# Uno.net
KiCad netlist of a schematic drawn in Altium Designer
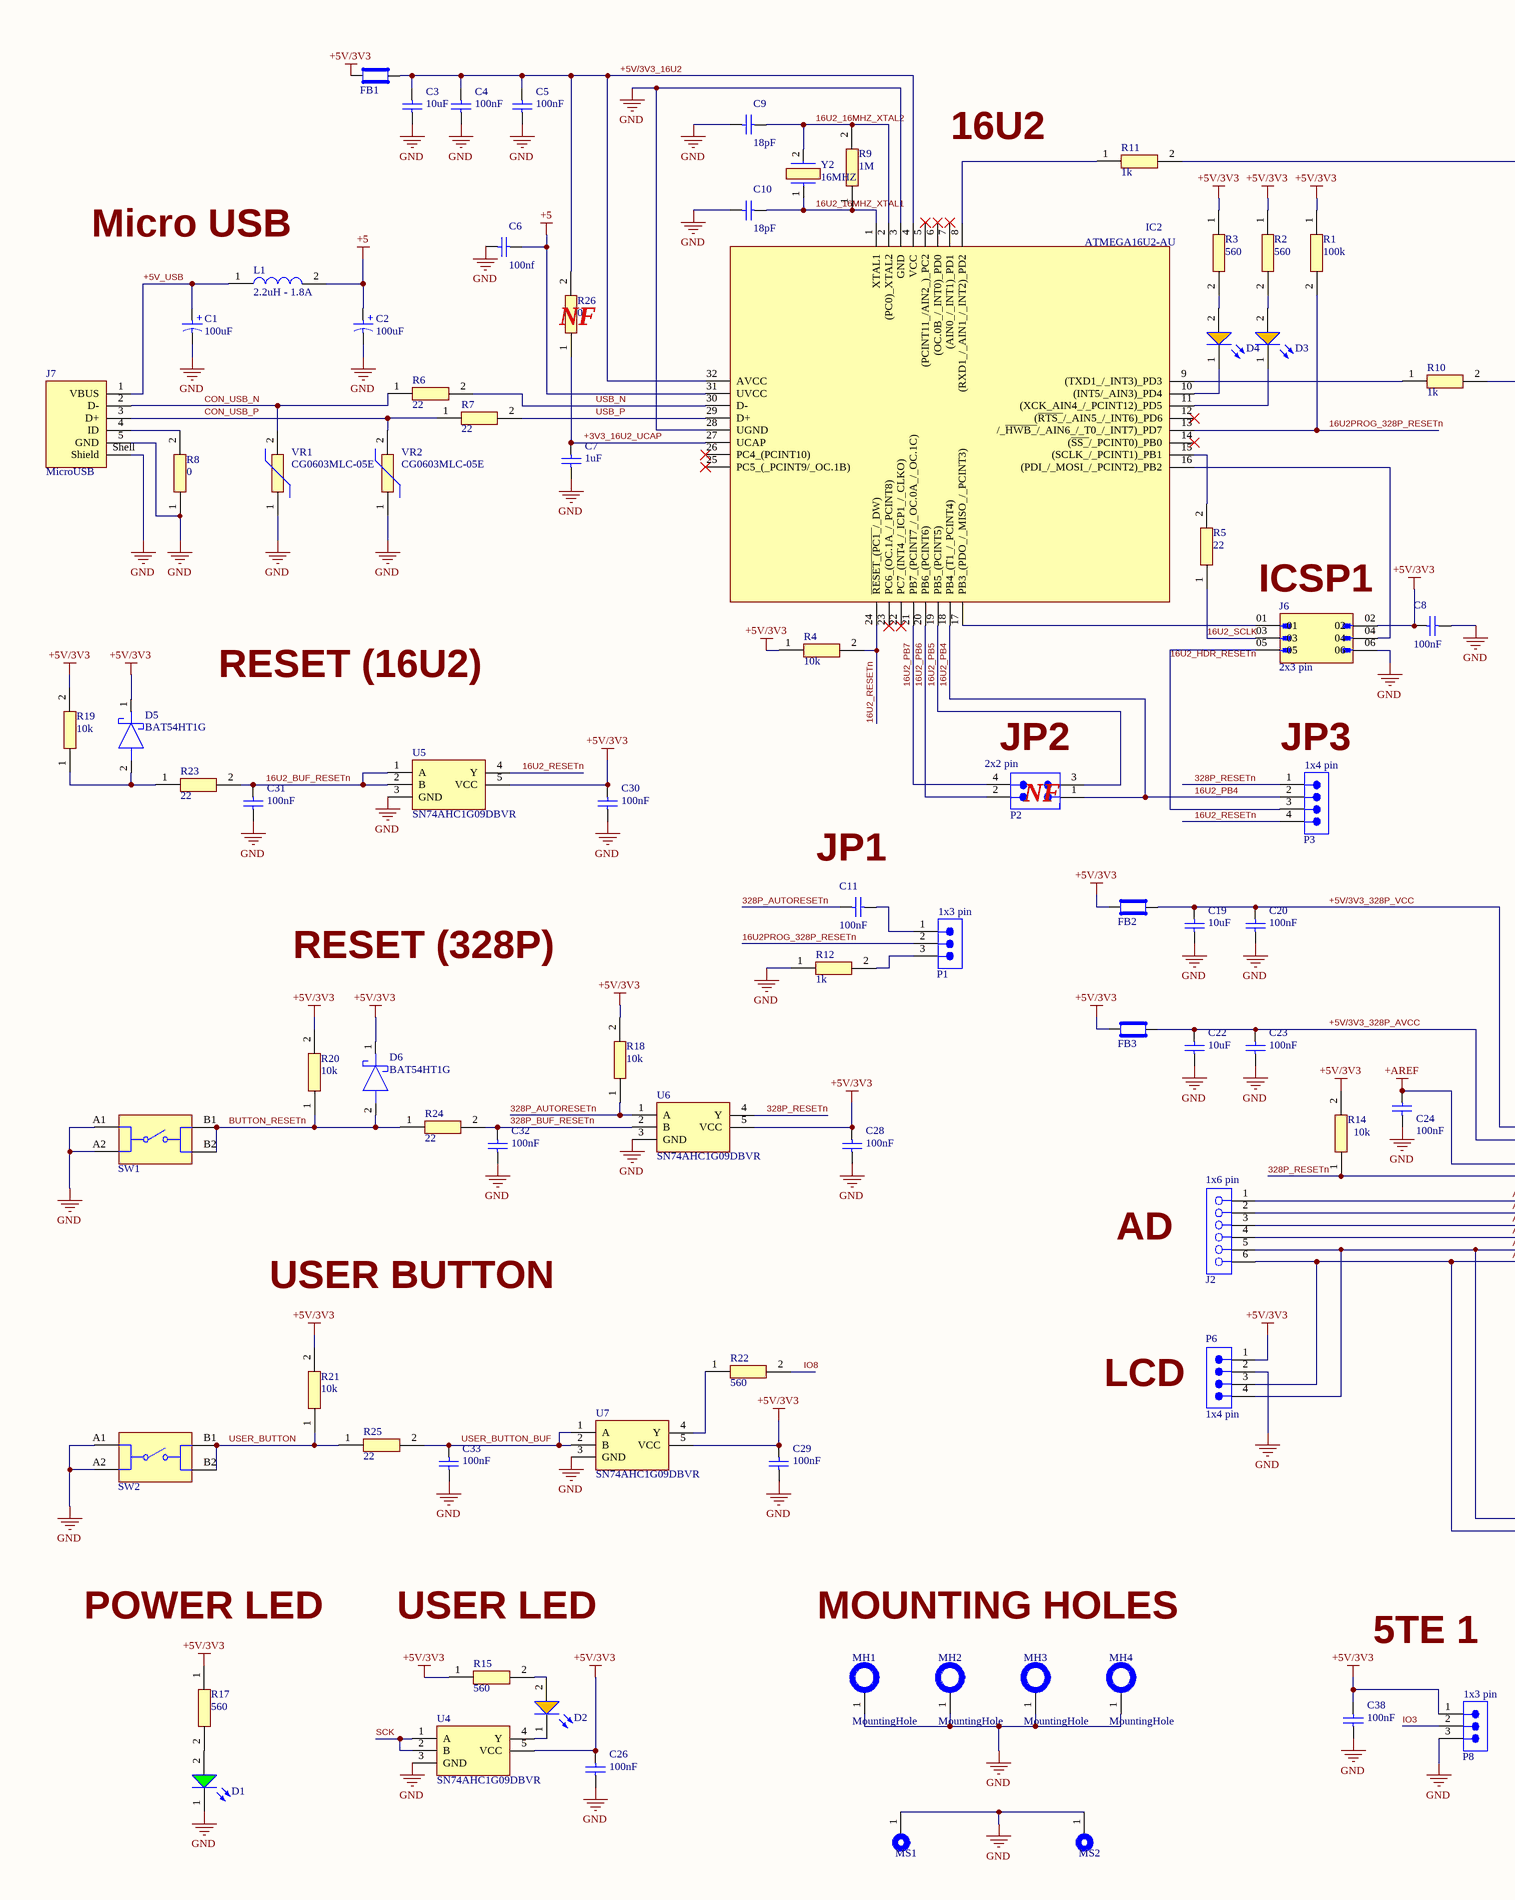
[diagram p0: Uno.SchDoc, left]
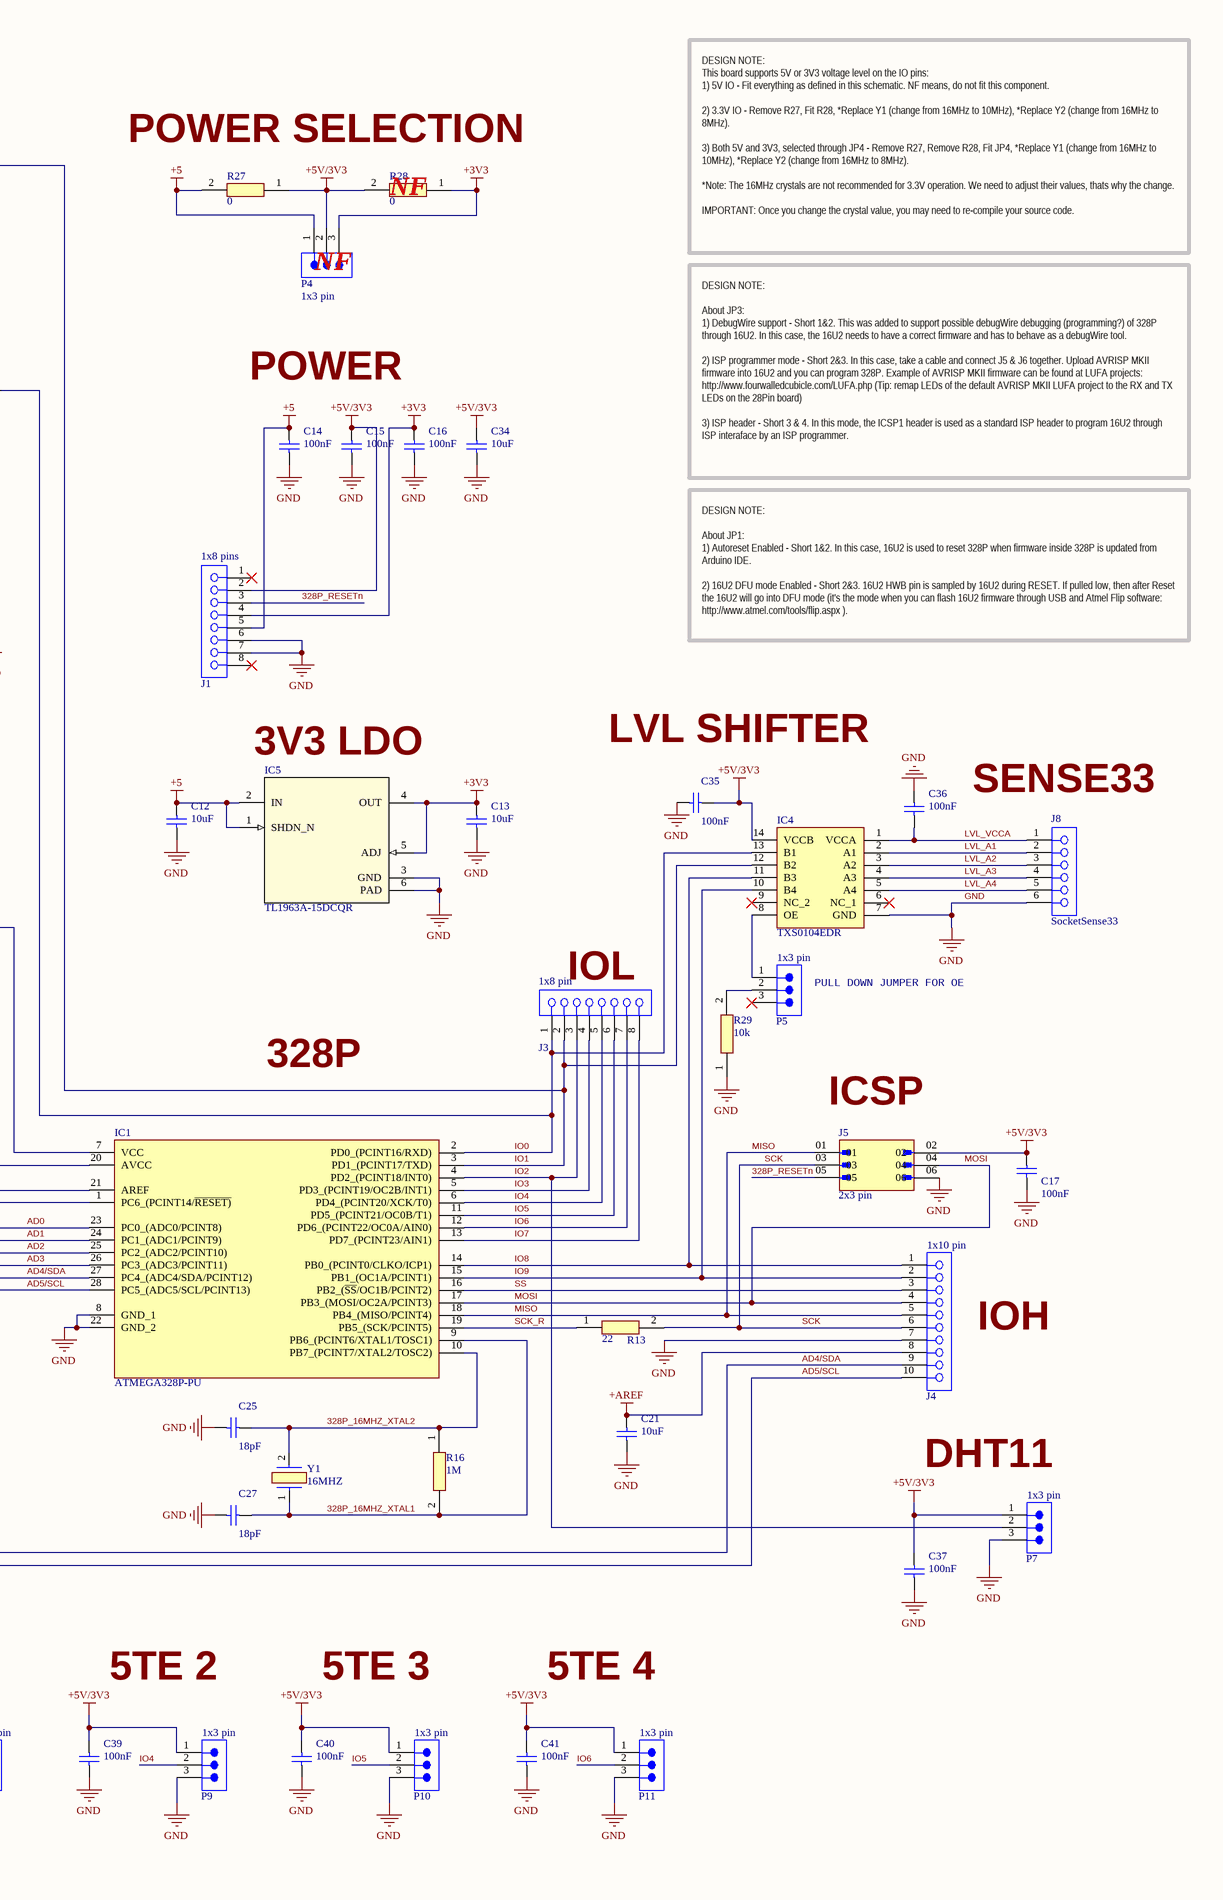
[diagram p1: Uno.SchDoc, right]

(export (version "E")
  (design (tool "Eeschema 10.0.6"))
  (components
    (comp (ref "C1")
      (value "100uF")
      (footprint "GH_PcbLib:WCAP-ASLI_D6.3H5.5")
      (description "WCAP-ASLI Aluminum Electrolytic Capacitor, V-Chip, D6.3 x H5.5mm, 100uF, 10V")
      (fields
        (field (name "MANUFACTURER PART NUMBER") "865080243007")
        (field (name "MANUFACTURER") "Wurth Elektronik")
      )
      (libsource (lib "GH_SchematicLib") (part "865080243007"))
    )
    (comp (ref "C2")
      (value "100uF")
      (footprint "GH_PcbLib:WCAP-ASLI_D6.3H5.5")
      (description "WCAP-ASLI Aluminum Electrolytic Capacitor, V-Chip, D6.3 x H5.5mm, 100uF, 10V")
      (fields
        (field (name "MANUFACTURER PART NUMBER") "865080243007")
        (field (name "MANUFACTURER") "Wurth Elektronik")
      )
      (libsource (lib "GH_SchematicLib") (part "865080243007"))
    )
    (comp (ref "C3")
      (value "10uF")
      (footprint "GH_PcbLib:WCAP_0805_L2W1.25H0.8")
      (fields
        (field (name "MANUFACTURER PART NUMBER") "885012004001")
        (field (name "MANUFACTURER") "Wurth Elektronik")
      )
      (libsource (lib "GH_SchematicLib") (part "CeramicCap"))
    )
    (comp (ref "C4")
      (value "100nF")
      (footprint "GH_PcbLib:WCAP_0805_L2W1.25H0.8")
      (fields
        (field (name "MANUFACTURER PART NUMBER") "885012004001")
        (field (name "MANUFACTURER") "Wurth Elektronik")
      )
      (libsource (lib "GH_SchematicLib") (part "CeramicCap"))
    )
    (comp (ref "C5")
      (value "100nF")
      (footprint "GH_PcbLib:WCAP_0805_L2W1.25H0.8")
      (fields
        (field (name "MANUFACTURER PART NUMBER") "885012004001")
        (field (name "MANUFACTURER") "Wurth Elektronik")
      )
      (libsource (lib "GH_SchematicLib") (part "CeramicCap"))
    )
    (comp (ref "C6")
      (value "100nf")
      (footprint "GH_PcbLib:WCAP_0805_L2W1.25H0.8")
      (fields
        (field (name "MANUFACTURER PART NUMBER") "885012004001")
        (field (name "MANUFACTURER") "Wurth Elektronik")
      )
      (libsource (lib "GH_SchematicLib") (part "CeramicCap"))
    )
    (comp (ref "C7")
      (value "1uF")
      (footprint "GH_PcbLib:WCAP_0805_L2W1.25H0.8")
      (fields
        (field (name "MANUFACTURER PART NUMBER") "885012004001")
        (field (name "MANUFACTURER") "Wurth Elektronik")
      )
      (libsource (lib "GH_SchematicLib") (part "CeramicCap"))
    )
    (comp (ref "C8")
      (value "100nF")
      (footprint "GH_PcbLib:WCAP_0805_L2W1.25H0.8")
      (fields
        (field (name "MANUFACTURER PART NUMBER") "885012004001")
        (field (name "MANUFACTURER") "Wurth Elektronik")
      )
      (libsource (lib "GH_SchematicLib") (part "CeramicCap"))
    )
    (comp (ref "C9")
      (value "18pF")
      (footprint "GH_PcbLib:WCAP_0805_L2W1.25H0.8")
      (fields
        (field (name "MANUFACTURER PART NUMBER") "885012004001")
        (field (name "MANUFACTURER") "Wurth Elektronik")
      )
      (libsource (lib "GH_SchematicLib") (part "CeramicCap"))
    )
    (comp (ref "C10")
      (value "18pF")
      (footprint "GH_PcbLib:WCAP_0805_L2W1.25H0.8")
      (fields
        (field (name "MANUFACTURER PART NUMBER") "885012004001")
        (field (name "MANUFACTURER") "Wurth Elektronik")
      )
      (libsource (lib "GH_SchematicLib") (part "CeramicCap"))
    )
    (comp (ref "C11")
      (value "100nF")
      (footprint "GH_PcbLib:WCAP_0805_L2W1.25H0.8")
      (fields
        (field (name "MANUFACTURER PART NUMBER") "885012004001")
        (field (name "MANUFACTURER") "Wurth Elektronik")
      )
      (libsource (lib "GH_SchematicLib") (part "CeramicCap"))
    )
    (comp (ref "C12")
      (value "10uF")
      (footprint "GH_PcbLib:WCAP_0805_L2W1.25H0.8")
      (fields
        (field (name "MANUFACTURER PART NUMBER") "885012004001")
        (field (name "MANUFACTURER") "Wurth Elektronik")
      )
      (libsource (lib "GH_SchematicLib") (part "CeramicCap"))
    )
    (comp (ref "C13")
      (value "10uF")
      (footprint "GH_PcbLib:WCAP_0805_L2W1.25H0.8")
      (fields
        (field (name "MANUFACTURER PART NUMBER") "885012004001")
        (field (name "MANUFACTURER") "Wurth Elektronik")
      )
      (libsource (lib "GH_SchematicLib") (part "CeramicCap"))
    )
    (comp (ref "C14")
      (value "100nF")
      (footprint "GH_PcbLib:WCAP_0805_L2W1.25H0.8")
      (fields
        (field (name "MANUFACTURER PART NUMBER") "885012004001")
        (field (name "MANUFACTURER") "Wurth Elektronik")
      )
      (libsource (lib "GH_SchematicLib") (part "CeramicCap"))
    )
    (comp (ref "C15")
      (value "100nF")
      (footprint "GH_PcbLib:WCAP_0805_L2W1.25H0.8")
      (fields
        (field (name "MANUFACTURER PART NUMBER") "885012004001")
        (field (name "MANUFACTURER") "Wurth Elektronik")
      )
      (libsource (lib "GH_SchematicLib") (part "CeramicCap"))
    )
    (comp (ref "C16")
      (value "100nF")
      (footprint "GH_PcbLib:WCAP_0805_L2W1.25H0.8")
      (fields
        (field (name "MANUFACTURER PART NUMBER") "885012004001")
        (field (name "MANUFACTURER") "Wurth Elektronik")
      )
      (libsource (lib "GH_SchematicLib") (part "CeramicCap"))
    )
    (comp (ref "C17")
      (value "100nF")
      (footprint "GH_PcbLib:WCAP_0805_L2W1.25H0.8")
      (fields
        (field (name "MANUFACTURER PART NUMBER") "885012004001")
        (field (name "MANUFACTURER") "Wurth Elektronik")
      )
      (libsource (lib "GH_SchematicLib") (part "CeramicCap"))
    )
    (comp (ref "C19")
      (value "10uF")
      (footprint "GH_PcbLib:WCAP_0805_L2W1.25H0.8")
      (fields
        (field (name "MANUFACTURER PART NUMBER") "885012004001")
        (field (name "MANUFACTURER") "Wurth Elektronik")
      )
      (libsource (lib "GH_SchematicLib") (part "CeramicCap"))
    )
    (comp (ref "C20")
      (value "100nF")
      (footprint "GH_PcbLib:WCAP_0805_L2W1.25H0.8")
      (fields
        (field (name "MANUFACTURER PART NUMBER") "885012004001")
        (field (name "MANUFACTURER") "Wurth Elektronik")
      )
      (libsource (lib "GH_SchematicLib") (part "CeramicCap"))
    )
    (comp (ref "C21")
      (value "10uF")
      (footprint "GH_PcbLib:WCAP_0805_L2W1.25H0.8")
      (fields
        (field (name "MANUFACTURER PART NUMBER") "885012004001")
        (field (name "MANUFACTURER") "Wurth Elektronik")
      )
      (libsource (lib "GH_SchematicLib") (part "CeramicCap"))
    )
    (comp (ref "C22")
      (value "10uF")
      (footprint "GH_PcbLib:WCAP_0805_L2W1.25H0.8")
      (fields
        (field (name "MANUFACTURER PART NUMBER") "885012004001")
        (field (name "MANUFACTURER") "Wurth Elektronik")
      )
      (libsource (lib "GH_SchematicLib") (part "CeramicCap"))
    )
    (comp (ref "C23")
      (value "100nF")
      (footprint "GH_PcbLib:WCAP_0805_L2W1.25H0.8")
      (fields
        (field (name "MANUFACTURER PART NUMBER") "885012004001")
        (field (name "MANUFACTURER") "Wurth Elektronik")
      )
      (libsource (lib "GH_SchematicLib") (part "CeramicCap"))
    )
    (comp (ref "C24")
      (value "100nF")
      (footprint "GH_PcbLib:WCAP_0805_L2W1.25H0.8")
      (fields
        (field (name "MANUFACTURER PART NUMBER") "885012004001")
        (field (name "MANUFACTURER") "Wurth Elektronik")
      )
      (libsource (lib "GH_SchematicLib") (part "CeramicCap"))
    )
    (comp (ref "C25")
      (value "18pF")
      (footprint "GH_PcbLib:WCAP_0805_L2W1.25H0.8")
      (fields
        (field (name "MANUFACTURER PART NUMBER") "885012004001")
        (field (name "MANUFACTURER") "Wurth Elektronik")
      )
      (libsource (lib "GH_SchematicLib") (part "CeramicCap"))
    )
    (comp (ref "C26")
      (value "100nF")
      (footprint "GH_PcbLib:WCAP_0805_L2W1.25H0.8")
      (fields
        (field (name "MANUFACTURER PART NUMBER") "885012004001")
        (field (name "MANUFACTURER") "Wurth Elektronik")
      )
      (libsource (lib "GH_SchematicLib") (part "CeramicCap"))
    )
    (comp (ref "C27")
      (value "18pF")
      (footprint "GH_PcbLib:WCAP_0805_L2W1.25H0.8")
      (fields
        (field (name "MANUFACTURER PART NUMBER") "885012004001")
        (field (name "MANUFACTURER") "Wurth Elektronik")
      )
      (libsource (lib "GH_SchematicLib") (part "CeramicCap"))
    )
    (comp (ref "C28")
      (value "100nF")
      (footprint "GH_PcbLib:WCAP_0805_L2W1.25H0.8")
      (fields
        (field (name "MANUFACTURER PART NUMBER") "885012004001")
        (field (name "MANUFACTURER") "Wurth Elektronik")
      )
      (libsource (lib "GH_SchematicLib") (part "CeramicCap"))
    )
    (comp (ref "C29")
      (value "100nF")
      (footprint "GH_PcbLib:WCAP_0805_L2W1.25H0.8")
      (fields
        (field (name "MANUFACTURER PART NUMBER") "885012004001")
        (field (name "MANUFACTURER") "Wurth Elektronik")
      )
      (libsource (lib "GH_SchematicLib") (part "CeramicCap"))
    )
    (comp (ref "C30")
      (value "100nF")
      (footprint "GH_PcbLib:WCAP_0805_L2W1.25H0.8")
      (fields
        (field (name "MANUFACTURER PART NUMBER") "885012004001")
        (field (name "MANUFACTURER") "Wurth Elektronik")
      )
      (libsource (lib "GH_SchematicLib") (part "CeramicCap"))
    )
    (comp (ref "C31")
      (value "100nF")
      (footprint "GH_PcbLib:WCAP_0805_L2W1.25H0.8")
      (fields
        (field (name "MANUFACTURER PART NUMBER") "885012004001")
        (field (name "MANUFACTURER") "Wurth Elektronik")
      )
      (libsource (lib "GH_SchematicLib") (part "CeramicCap"))
    )
    (comp (ref "C32")
      (value "100nF")
      (footprint "GH_PcbLib:WCAP_0805_L2W1.25H0.8")
      (fields
        (field (name "MANUFACTURER PART NUMBER") "885012004001")
        (field (name "MANUFACTURER") "Wurth Elektronik")
      )
      (libsource (lib "GH_SchematicLib") (part "CeramicCap"))
    )
    (comp (ref "C33")
      (value "100nF")
      (footprint "GH_PcbLib:WCAP_0805_L2W1.25H0.8")
      (fields
        (field (name "MANUFACTURER PART NUMBER") "885012004001")
        (field (name "MANUFACTURER") "Wurth Elektronik")
      )
      (libsource (lib "GH_SchematicLib") (part "CeramicCap"))
    )
    (comp (ref "C34")
      (value "10uF")
      (footprint "GH_PcbLib:WCAP_0805_L2W1.25H0.8")
      (fields
        (field (name "MANUFACTURER PART NUMBER") "885012004001")
        (field (name "MANUFACTURER") "Wurth Elektronik")
      )
      (libsource (lib "GH_SchematicLib") (part "CeramicCap"))
    )
    (comp (ref "C35")
      (value "100nF")
      (footprint "GH_PcbLib:WCAP_0805_L2W1.25H0.8")
      (fields
        (field (name "MANUFACTURER PART NUMBER") "885012004001")
        (field (name "MANUFACTURER") "Wurth Elektronik")
      )
      (libsource (lib "GH_SchematicLib") (part "CeramicCap"))
    )
    (comp (ref "C36")
      (value "100nF")
      (footprint "GH_PcbLib:WCAP_0805_L2W1.25H0.8")
      (fields
        (field (name "MANUFACTURER PART NUMBER") "885012004001")
        (field (name "MANUFACTURER") "Wurth Elektronik")
      )
      (libsource (lib "GH_SchematicLib") (part "CeramicCap"))
    )
    (comp (ref "C37")
      (value "100nF")
      (footprint "GH_PcbLib:WCAP_0805_L2W1.25H0.8")
      (fields
        (field (name "MANUFACTURER PART NUMBER") "885012004001")
        (field (name "MANUFACTURER") "Wurth Elektronik")
      )
      (libsource (lib "GH_SchematicLib") (part "CeramicCap"))
    )
    (comp (ref "C38")
      (value "100nF")
      (footprint "GH_PcbLib:WCAP_0805_L2W1.25H0.8")
      (fields
        (field (name "MANUFACTURER PART NUMBER") "885012004001")
        (field (name "MANUFACTURER") "Wurth Elektronik")
      )
      (libsource (lib "GH_SchematicLib") (part "CeramicCap"))
    )
    (comp (ref "C39")
      (value "100nF")
      (footprint "GH_PcbLib:WCAP_0805_L2W1.25H0.8")
      (fields
        (field (name "MANUFACTURER PART NUMBER") "885012004001")
        (field (name "MANUFACTURER") "Wurth Elektronik")
      )
      (libsource (lib "GH_SchematicLib") (part "CeramicCap"))
    )
    (comp (ref "C40")
      (value "100nF")
      (footprint "GH_PcbLib:WCAP_0805_L2W1.25H0.8")
      (fields
        (field (name "MANUFACTURER PART NUMBER") "885012004001")
        (field (name "MANUFACTURER") "Wurth Elektronik")
      )
      (libsource (lib "GH_SchematicLib") (part "CeramicCap"))
    )
    (comp (ref "C41")
      (value "100nF")
      (footprint "GH_PcbLib:WCAP_0805_L2W1.25H0.8")
      (fields
        (field (name "MANUFACTURER PART NUMBER") "885012004001")
        (field (name "MANUFACTURER") "Wurth Elektronik")
      )
      (libsource (lib "GH_SchematicLib") (part "CeramicCap"))
    )
    (comp (ref "D1")
      (value "Green, 3.2V, 140°")
      (footprint "GH_PcbLib:WL-SMCW_0805_150080xx75000")
      (description "WL-SMCW Mono-color Chip LED Waterclear, size 0805, Green, 3.2V, 140°")
      (fields
        (field (name "MANUFACTURER PART NUMBER") "150080GS75000")
        (field (name "MANUFACTURER") "Wurth Elektronik")
      )
      (libsource (lib "GH_SchematicLib") (part "150080GS75000"))
    )
    (comp (ref "D2")
      (value "Amber, 2V, 140°")
      (footprint "GH_PcbLib:WL-SMCW_0805_150080xx75000")
      (description "WL-SMCW Mono-color Chip LED Waterclear, size 0805, Amber, 2V, 140°")
      (fields
        (field (name "MANUFACTURER PART NUMBER") "150080AS75000")
        (field (name "MANUFACTURER") "Wurth Elektronik")
      )
      (libsource (lib "GH_SchematicLib") (part "150080AS75000"))
    )
    (comp (ref "D3")
      (value "Amber, 2V, 140°")
      (footprint "GH_PcbLib:WL-SMCW_0805_150080xx75000")
      (description "WL-SMCW Mono-color Chip LED Waterclear, size 0805, Amber, 2V, 140°")
      (fields
        (field (name "MANUFACTURER PART NUMBER") "150080AS75000")
        (field (name "MANUFACTURER") "Wurth Elektronik")
      )
      (libsource (lib "GH_SchematicLib") (part "150080AS75000"))
    )
    (comp (ref "D4")
      (value "Amber, 2V, 140°")
      (footprint "GH_PcbLib:WL-SMCW_0805_150080xx75000")
      (description "WL-SMCW Mono-color Chip LED Waterclear, size 0805, Amber, 2V, 140°")
      (fields
        (field (name "MANUFACTURER PART NUMBER") "150080AS75000")
        (field (name "MANUFACTURER") "Wurth Elektronik")
      )
      (libsource (lib "GH_SchematicLib") (part "150080AS75000"))
    )
    (comp (ref "D5")
      (value "BAT54HT1G")
      (footprint "GH_PcbLib:SOD2512X110N")
      (description "Diode Shotkey")
      (fields (field (name "MOUSER PART NUMBER") "863-BAT54HT1G"))
      (libsource (lib "GH_SchematicLib") (part "BAT54HT1G"))
    )
    (comp (ref "D6")
      (value "BAT54HT1G")
      (footprint "GH_PcbLib:SOD2512X110N")
      (description "Diode Shotkey")
      (fields (field (name "MOUSER PART NUMBER") "863-BAT54HT1G"))
      (libsource (lib "GH_SchematicLib") (part "BAT54HT1G"))
    )
    (comp (ref "FB1")
      (value "74279204")
      (footprint "GH_PcbLib:WE-CBF_0805_L2W1.2H0.9_HS/WB")
      (description "WE-CBF SMT EMI Suppression Ferrite Bead, size 0805, 600Ohm, 1.5A")
      (fields (field (name "MANUFACTURER") "Wurth Elektronik"))
      (libsource (lib "GH_SchematicLib") (part "74279204"))
    )
    (comp (ref "FB2")
      (value "74279204")
      (footprint "GH_PcbLib:WE-CBF_0805_L2W1.2H0.9_HS/WB")
      (description "WE-CBF SMT EMI Suppression Ferrite Bead, size 0805, 600Ohm, 1.5A")
      (fields (field (name "MANUFACTURER") "Wurth Elektronik"))
      (libsource (lib "GH_SchematicLib") (part "74279204"))
    )
    (comp (ref "FB3")
      (value "74279204")
      (footprint "GH_PcbLib:WE-CBF_0805_L2W1.2H0.9_HS/WB")
      (description "WE-CBF SMT EMI Suppression Ferrite Bead, size 0805, 600Ohm, 1.5A")
      (fields (field (name "MANUFACTURER") "Wurth Elektronik"))
      (libsource (lib "GH_SchematicLib") (part "74279204"))
    )
    (comp (ref "IC1")
      (value "ATMEGA328P-PU")
      (footprint "DIP794W53P254L3467H457Q28N")
      (description "MICROCHIP - ATMEGA328P-PU. - MICROCONTROLLER MCU, 8 BIT, ATMEGA, 20MHZ, DIP-28")
      (fields (field (name "MOUSER PART NUMBER") "556-ATMEGA328P-PU"))
      (libsource (lib "GH_SchematicLib") (part "ATMEGA328P-PU"))
    )
    (comp (ref "IC2")
      (value "ATMEGA16U2-AU")
      (footprint "SamacSys:QFP80P900X900X120-32N")
      (description "Integrated Circuit")
      (fields (field (name "MOUSER PART NUMBER") "556-ATMEGA16U2-AU"))
      (libsource (lib "*") (part "ATMEGA16U2-AU"))
    )
    (comp (ref "IC4")
      (value "TXS0104EDR")
      (footprint "GH_PcbLib:SOIC127P600X175-14N")
      (description "Integrated Circuit")
      (fields (field (name "MOUSER PART NUMBER") "595-TXS0104EDR"))
      (libsource (lib "GH_SchematicLib") (part "TXS0104EDR"))
    )
    (comp (ref "IC5")
      (value "TL1963A-15DCQR")
      (footprint "GH_PcbLib:DCQ0006A_M")
      (description "3v3 LDO")
      (fields (field (name "PARTNUMBER") "TL1963ADCQR") (field (name "ALTERNATE_PARTNUMBER") "TL1963ADCQT"))
      (libsource (lib "GH_SchematicLib") (part "TL1963A-15DCQR"))
    )
    (comp (ref "J1")
      (value "1x8 pins")
      (footprint "GH_PcbLib:61300811821")
      (description "61300811821 WR-PHD Socket Header, THT, Vertical, pitch 2.54mm, 1 Row, 8P")
      (fields
        (field (name "MANUFACTURER PART NUMBER") "61300811821")
        (field (name "MANUFACTURER") "Wurth Elektronik")
      )
      (libsource (lib "GH_SchematicLib") (part "61300811821"))
    )
    (comp (ref "J2")
      (value "1x6 pin")
      (footprint "GH_PcbLib:61300611821")
      (description "61300611821 WR-PHD Socket Header, THT, Vertical, pitch 2.54mm, 1 Row, 6P")
      (fields
        (field (name "MANUFACTURER PART NUMBER") "61300611821")
        (field (name "MANUFACTURER") "Wurth Elektronik")
      )
      (libsource (lib "GH_SchematicLib") (part "61300611821"))
    )
    (comp (ref "J3")
      (value "1x8 pin")
      (footprint "GH_PcbLib:61300811821")
      (description "61300811821 WR-PHD Socket Header, THT, Vertical, pitch 2.54mm, 1 Row, 8P")
      (fields
        (field (name "MANUFACTURER PART NUMBER") "61300811821")
        (field (name "MANUFACTURER") "Wurth Elektronik")
      )
      (libsource (lib "GH_SchematicLib") (part "61300811821"))
    )
    (comp (ref "J4")
      (value "1x10 pin")
      (footprint "GH_PcbLib:61301011821")
      (description "61301011821 WR-PHD Socket Header, THT, Vertical, pitch 2.54mm, 1 Row, 10P")
      (fields
        (field (name "MANUFACTURER PART NUMBER") "61301011821")
        (field (name "MANUFACTURER") "Wurth Elektronik")
      )
      (libsource (lib "GH_SchematicLib") (part "61301011821"))
    )
    (comp (ref "J5")
      (value "2x3 pin")
      (footprint "GH_PcbLib:AMPHENOL_67997-106HLF")
      (fields (field (name "MP") "67997-106HLF") (field (name "MF") "Amphenol ICC"))
      (libsource (lib "GH_SchematicLib") (part "67997-106HLF"))
    )
    (comp (ref "J6")
      (value "2x3 pin")
      (footprint "GH_PcbLib:AMPHENOL_67997-106HLF")
      (fields (field (name "MP") "67997-106HLF") (field (name "MF") "Amphenol ICC"))
      (libsource (lib "GH_SchematicLib") (part "67997-106HLF"))
    )
    (comp (ref "J7")
      (value "MicroUSB")
      (footprint "629105150521")
      (description "629105150521 WR-COM Micro USB 2.0 SMT Type B Horizontal 5 Contacts High Current")
      (fields
        (field (name "MANUFACTURER PART NUMBER") "629105150521")
        (field (name "MANUFACTURER") "Wurth Elektronik")
      )
      (libsource (lib "GH_SchematicLib") (part "629105150521"))
    )
    (comp (ref "J8")
      (value "SocketSense33")
      (footprint "GH_PcbLib:Socket_Sense33")
      (libsource (lib "GH_SchematicLib") (part "SocketSense33"))
    )
    (comp (ref "L1")
      (value "2.2uH - 1.8A")
      (footprint "GH_PcbLib:RESC2012X50N")
      (description "Power Inductors - SMD 0805 2.2uH 20%")
      (fields
        (field (name "MANUFACTURER_PART_NUMBER") "CI160808-R10J")
        (field (name "MOUSER PART NUMBER") "652-CI160808-R10J")
      )
      (libsource (lib "GH_SchematicLib") (part "Power Inductor"))
    )
    (comp (ref "MH1")
      (value "MountingHole")
      (footprint "Mounting Hole")
      (libsource (lib "GH_SchematicLib") (part "MountingHole"))
    )
    (comp (ref "MH2")
      (value "MountingHole")
      (footprint "Mounting Hole")
      (libsource (lib "GH_SchematicLib") (part "MountingHole"))
    )
    (comp (ref "MH3")
      (value "MountingHole")
      (footprint "Mounting Hole")
      (libsource (lib "GH_SchematicLib") (part "MountingHole"))
    )
    (comp (ref "MH4")
      (value "MountingHole")
      (footprint "Mounting Hole")
      (libsource (lib "GH_SchematicLib") (part "MountingHole"))
    )
    (comp (ref "MS1")
      (value "mech_Supp_USB")
      (footprint "Mech_Sup_USB")
      (libsource (lib "GH_SchematicLib") (part "mech_Supp_USB"))
    )
    (comp (ref "MS2")
      (value "mech_Supp_USB")
      (footprint "Mech_Sup_USB")
      (libsource (lib "GH_SchematicLib") (part "mech_Supp_USB"))
    )
    (comp (ref "P1")
      (value "1x3 pin")
      (footprint "GH_PcbLib:61300311121")
      (description "61300311121 WR-PHD Pin Header, THT, Vertical, pitch 2.54mm, 1 Row, 3P")
      (fields
        (field (name "MANUFACTURER PART NUMBER") "61300311121")
        (field (name "MANUFACTURER") "Wurth Elektronik")
      )
      (libsource (lib "GH_SchematicLib") (part "61300311121"))
    )
    (comp (ref "P2")
      (value "2x2 pin")
      (footprint "GH_PcbLib:61300421121")
      (description "61300421121 WR-PHD Pin Header, THT, Vertical, pitch 2.54mm, 2 Row, 4P")
      (fields
        (field (name "MANUFACTURER PART NUMBER") "61300421121")
        (field (name "MANUFACTURER") "Wurth Elektronik")
      )
      (libsource (lib "GH_SchematicLib") (part "61300421121"))
    )
    (comp (ref "P3")
      (value "1x4 pin")
      (footprint "GH_PcbLib:61300411121")
      (description "61300411121 WR-PHD Pin Header, THT, Vertical, pitch 2.54mm, 1 Row, 4P")
      (fields
        (field (name "MANUFACTURER PART NUMBER") "61300411121")
        (field (name "MANUFACTURER") "Wurth Elektronik")
      )
      (libsource (lib "GH_SchematicLib") (part "61300411121"))
    )
    (comp (ref "P4")
      (value "1x3 pin")
      (footprint "GH_PcbLib:61300311121")
      (description "61300311121 WR-PHD Pin Header, THT, Vertical, pitch 2.54mm, 1 Row, 3P")
      (fields
        (field (name "MANUFACTURER PART NUMBER") "61300311121")
        (field (name "MANUFACTURER") "Wurth Elektronik")
      )
      (libsource (lib "GH_SchematicLib") (part "61300311121"))
    )
    (comp (ref "P5")
      (value "1x3 pin")
      (footprint "GH_PcbLib:61300311121")
      (description "61300311121 WR-PHD Pin Header, THT, Vertical, pitch 2.54mm, 1 Row, 3P")
      (fields
        (field (name "MANUFACTURER PART NUMBER") "61300311121")
        (field (name "MANUFACTURER") "Wurth Elektronik")
      )
      (libsource (lib "GH_SchematicLib") (part "61300311121"))
    )
    (comp (ref "P6")
      (value "1x4 pin")
      (footprint "GH_PcbLib:61300411121")
      (description "61300411121 WR-PHD Pin Header, THT, Vertical, pitch 2.54mm, 1 Row, 4P")
      (fields
        (field (name "MANUFACTURER PART NUMBER") "61300411121")
        (field (name "MANUFACTURER") "Wurth Elektronik")
      )
      (libsource (lib "GH_SchematicLib") (part "61300411121"))
    )
    (comp (ref "P7")
      (value "1x3 pin")
      (footprint "GH_PcbLib:61300311121")
      (description "61300311121 WR-PHD Pin Header, THT, Vertical, pitch 2.54mm, 1 Row, 3P")
      (fields
        (field (name "MANUFACTURER PART NUMBER") "61300311121")
        (field (name "MANUFACTURER") "Wurth Elektronik")
      )
      (libsource (lib "GH_SchematicLib") (part "61300311121"))
    )
    (comp (ref "P8")
      (value "1x3 pin")
      (footprint "GH_PcbLib:61300311121")
      (description "61300311121 WR-PHD Pin Header, THT, Vertical, pitch 2.54mm, 1 Row, 3P")
      (fields
        (field (name "MANUFACTURER PART NUMBER") "61300311121")
        (field (name "MANUFACTURER") "Wurth Elektronik")
      )
      (libsource (lib "GH_SchematicLib") (part "61300311121"))
    )
    (comp (ref "P9")
      (value "1x3 pin")
      (footprint "GH_PcbLib:61300311121")
      (description "61300311121 WR-PHD Pin Header, THT, Vertical, pitch 2.54mm, 1 Row, 3P")
      (fields
        (field (name "MANUFACTURER PART NUMBER") "61300311121")
        (field (name "MANUFACTURER") "Wurth Elektronik")
      )
      (libsource (lib "GH_SchematicLib") (part "61300311121"))
    )
    (comp (ref "P10")
      (value "1x3 pin")
      (footprint "GH_PcbLib:61300311121")
      (description "61300311121 WR-PHD Pin Header, THT, Vertical, pitch 2.54mm, 1 Row, 3P")
      (fields
        (field (name "MANUFACTURER PART NUMBER") "61300311121")
        (field (name "MANUFACTURER") "Wurth Elektronik")
      )
      (libsource (lib "GH_SchematicLib") (part "61300311121"))
    )
    (comp (ref "P11")
      (value "1x3 pin")
      (footprint "GH_PcbLib:61300311121")
      (description "61300311121 WR-PHD Pin Header, THT, Vertical, pitch 2.54mm, 1 Row, 3P")
      (fields
        (field (name "MANUFACTURER PART NUMBER") "61300311121")
        (field (name "MANUFACTURER") "Wurth Elektronik")
      )
      (libsource (lib "GH_SchematicLib") (part "61300311121"))
    )
    (comp (ref "R1")
      (value "100k")
      (footprint "GH_PcbLib:RESC2012X50N")
      (description "Resistor 100k")
      (fields
        (field (name "MANUFACTURER_PART_NUMBER") "AC05000004707JAC00")
        (field (name "MOUSER PART NUMBER") "594-AC05W0R470J")
      )
      (libsource (lib "") (part "Resistor0805_2"))
    )
    (comp (ref "R2")
      (value "560")
      (footprint "GH_PcbLib:RESC2012X50N")
      (description "Resistor 560 Ohm")
      (fields
        (field (name "MANUFACTURER_PART_NUMBER") "AC05000004707JAC00")
        (field (name "MOUSER PART NUMBER") "594-AC05W0R470J")
      )
      (libsource (lib "") (part "Resistor0805_2"))
    )
    (comp (ref "R3")
      (value "560")
      (footprint "GH_PcbLib:RESC2012X50N")
      (description "Resistor 560 Ohm")
      (fields
        (field (name "MANUFACTURER_PART_NUMBER") "AC05000004707JAC00")
        (field (name "MOUSER PART NUMBER") "594-AC05W0R470J")
      )
      (libsource (lib "") (part "Resistor0805_2"))
    )
    (comp (ref "R4")
      (value "10k")
      (footprint "GH_PcbLib:RESC2012X50N")
      (description "Resistor 10k")
      (fields
        (field (name "MANUFACTURER_PART_NUMBER") "AC05000004707JAC00")
        (field (name "MOUSER PART NUMBER") "594-AC05W0R470J")
      )
      (libsource (lib "") (part "Resistor0805_1"))
    )
    (comp (ref "R5")
      (value "22")
      (footprint "GH_PcbLib:RESC2012X50N")
      (description "Resistor 22")
      (fields
        (field (name "MANUFACTURER_PART_NUMBER") "AC05000004707JAC00")
        (field (name "MOUSER PART NUMBER") "594-AC05W0R470J")
      )
      (libsource (lib "GH_SchematicLib") (part "Resistor0805"))
    )
    (comp (ref "R6")
      (value "22")
      (footprint "GH_PcbLib:RESC2012X50N")
      (description "Resistor 22Ohm")
      (fields
        (field (name "MANUFACTURER_PART_NUMBER") "AC05000004707JAC00")
        (field (name "MOUSER PART NUMBER") "594-AC05W0R470J")
      )
      (libsource (lib "") (part "Resistor0805_1"))
    )
    (comp (ref "R7")
      (value "22")
      (footprint "GH_PcbLib:RESC2012X50N")
      (description "Resistor 22Ohm")
      (fields
        (field (name "MANUFACTURER_PART_NUMBER") "AC05000004707JAC00")
        (field (name "MOUSER PART NUMBER") "594-AC05W0R470J")
      )
      (libsource (lib "") (part "Resistor0805_1"))
    )
    (comp (ref "R8")
      (value "0")
      (footprint "GH_PcbLib:RESC2012X50N")
      (description "Resistor 0 Ohm")
      (fields
        (field (name "MANUFACTURER_PART_NUMBER") "AC05000004707JAC00")
        (field (name "MOUSER PART NUMBER") "594-AC05W0R470J")
      )
      (libsource (lib "GH_SchematicLib") (part "Resistor0805"))
    )
    (comp (ref "R9")
      (value "1M")
      (footprint "GH_PcbLib:RESC2012X50N")
      (description "Resistor 1M")
      (fields
        (field (name "MANUFACTURER_PART_NUMBER") "AC05000004707JAC00")
        (field (name "MOUSER PART NUMBER") "594-AC05W0R470J")
      )
      (libsource (lib "GH_SchematicLib") (part "Resistor0805"))
    )
    (comp (ref "R10")
      (value "1k")
      (footprint "GH_PcbLib:RESC2012X50N")
      (description "Resistor 10k")
      (fields
        (field (name "MANUFACTURER_PART_NUMBER") "AC05000004707JAC00")
        (field (name "MOUSER PART NUMBER") "594-AC05W0R470J")
      )
      (libsource (lib "") (part "Resistor0805_1"))
    )
    (comp (ref "R11")
      (value "1k")
      (footprint "GH_PcbLib:RESC2012X50N")
      (description "Resistor 10k")
      (fields
        (field (name "MANUFACTURER_PART_NUMBER") "AC05000004707JAC00")
        (field (name "MOUSER PART NUMBER") "594-AC05W0R470J")
      )
      (libsource (lib "") (part "Resistor0805_1"))
    )
    (comp (ref "R12")
      (value "1k")
      (footprint "GH_PcbLib:RESC2012X50N")
      (description "Resistor 10k")
      (fields
        (field (name "MANUFACTURER_PART_NUMBER") "AC05000004707JAC00")
        (field (name "MOUSER PART NUMBER") "594-AC05W0R470J")
      )
      (libsource (lib "") (part "Resistor0805_1"))
    )
    (comp (ref "R13")
      (value "22")
      (footprint "GH_PcbLib:RESC2012X50N")
      (description "Resistor 22Ohm")
      (fields
        (field (name "MANUFACTURER_PART_NUMBER") "AC05000004707JAC00")
        (field (name "MOUSER PART NUMBER") "594-AC05W0R470J")
      )
      (libsource (lib "") (part "Resistor0805_1"))
    )
    (comp (ref "R14")
      (value "10k")
      (footprint "GH_PcbLib:RESC2012X50N")
      (description "Resistor 10k")
      (fields
        (field (name "MANUFACTURER_PART_NUMBER") "AC05000004707JAC00")
        (field (name "MOUSER PART NUMBER") "594-AC05W0R470J")
      )
      (libsource (lib "GH_SchematicLib") (part "Resistor0805"))
    )
    (comp (ref "R15")
      (value "560")
      (footprint "GH_PcbLib:RESC2012X50N")
      (description "Resistor 560 Ohm")
      (fields
        (field (name "MANUFACTURER_PART_NUMBER") "AC05000004707JAC00")
        (field (name "MOUSER PART NUMBER") "594-AC05W0R470J")
      )
      (libsource (lib "") (part "Resistor0805_1"))
    )
    (comp (ref "R16")
      (value "1M")
      (footprint "GH_PcbLib:RESC2012X50N")
      (description "Resistor 1M")
      (fields
        (field (name "MANUFACTURER_PART_NUMBER") "AC05000004707JAC00")
        (field (name "MOUSER PART NUMBER") "594-AC05W0R470J")
      )
      (libsource (lib "") (part "Resistor0805_2"))
    )
    (comp (ref "R17")
      (value "560")
      (footprint "GH_PcbLib:RESC2012X50N")
      (description "Resistor 560 Ohm")
      (fields
        (field (name "MANUFACTURER_PART_NUMBER") "AC05000004707JAC00")
        (field (name "MOUSER PART NUMBER") "594-AC05W0R470J")
      )
      (libsource (lib "") (part "Resistor0805_2"))
    )
    (comp (ref "R18")
      (value "10k")
      (footprint "GH_PcbLib:RESC2012X50N")
      (description "Resistor 10k")
      (fields
        (field (name "MANUFACTURER_PART_NUMBER") "AC05000004707JAC00")
        (field (name "MOUSER PART NUMBER") "594-AC05W0R470J")
      )
      (libsource (lib "GH_SchematicLib") (part "Resistor0805"))
    )
    (comp (ref "R19")
      (value "10k")
      (footprint "GH_PcbLib:RESC2012X50N")
      (description "Resistor 10k")
      (fields
        (field (name "MANUFACTURER_PART_NUMBER") "AC05000004707JAC00")
        (field (name "MOUSER PART NUMBER") "594-AC05W0R470J")
      )
      (libsource (lib "GH_SchematicLib") (part "Resistor0805"))
    )
    (comp (ref "R20")
      (value "10k")
      (footprint "GH_PcbLib:RESC2012X50N")
      (description "Resistor 10k")
      (fields
        (field (name "MANUFACTURER_PART_NUMBER") "AC05000004707JAC00")
        (field (name "MOUSER PART NUMBER") "594-AC05W0R470J")
      )
      (libsource (lib "GH_SchematicLib") (part "Resistor0805"))
    )
    (comp (ref "R21")
      (value "10k")
      (footprint "GH_PcbLib:RESC2012X50N")
      (description "Resistor 10k")
      (fields
        (field (name "MANUFACTURER_PART_NUMBER") "AC05000004707JAC00")
        (field (name "MOUSER PART NUMBER") "594-AC05W0R470J")
      )
      (libsource (lib "GH_SchematicLib") (part "Resistor0805"))
    )
    (comp (ref "R22")
      (value "560")
      (footprint "GH_PcbLib:RESC2012X50N")
      (description "Resistor 560 Ohm")
      (fields
        (field (name "MANUFACTURER_PART_NUMBER") "AC05000004707JAC00")
        (field (name "MOUSER PART NUMBER") "594-AC05W0R470J")
      )
      (libsource (lib "") (part "Resistor0805_1"))
    )
    (comp (ref "R23")
      (value "22")
      (footprint "GH_PcbLib:RESC2012X50N")
      (description "Resistor 22Ohm")
      (fields
        (field (name "MANUFACTURER_PART_NUMBER") "AC05000004707JAC00")
        (field (name "MOUSER PART NUMBER") "594-AC05W0R470J")
      )
      (libsource (lib "") (part "Resistor0805_1"))
    )
    (comp (ref "R24")
      (value "22")
      (footprint "GH_PcbLib:RESC2012X50N")
      (description "Resistor 22Ohm")
      (fields
        (field (name "MANUFACTURER_PART_NUMBER") "AC05000004707JAC00")
        (field (name "MOUSER PART NUMBER") "594-AC05W0R470J")
      )
      (libsource (lib "") (part "Resistor0805_1"))
    )
    (comp (ref "R25")
      (value "22")
      (footprint "GH_PcbLib:RESC2012X50N")
      (description "Resistor 22Ohm")
      (fields
        (field (name "MANUFACTURER_PART_NUMBER") "AC05000004707JAC00")
        (field (name "MOUSER PART NUMBER") "594-AC05W0R470J")
      )
      (libsource (lib "") (part "Resistor0805_1"))
    )
    (comp (ref "R26")
      (value "0")
      (footprint "GH_PcbLib:RESC2012X50N")
      (description "Resistor 0 Ohm")
      (fields
        (field (name "MANUFACTURER_PART_NUMBER") "AC05000004707JAC00")
        (field (name "MOUSER PART NUMBER") "594-AC05W0R470J")
      )
      (libsource (lib "GH_SchematicLib") (part "Resistor0805"))
    )
    (comp (ref "R27")
      (value "0")
      (footprint "GH_PcbLib:RESC2012X50N")
      (description "Resistor 0 Ohm")
      (fields
        (field (name "MANUFACTURER_PART_NUMBER") "AC05000004707JAC00")
        (field (name "MOUSER PART NUMBER") "594-AC05W0R470J")
      )
      (libsource (lib "") (part "Resistor0805_3"))
    )
    (comp (ref "R28")
      (value "0")
      (footprint "GH_PcbLib:RESC2012X50N")
      (description "Resistor 0 Ohm")
      (fields
        (field (name "MANUFACTURER_PART_NUMBER") "AC05000004707JAC00")
        (field (name "MOUSER PART NUMBER") "594-AC05W0R470J")
      )
      (libsource (lib "") (part "Resistor0805_3"))
    )
    (comp (ref "R29")
      (value "10k")
      (footprint "GH_PcbLib:RESC2012X50N")
      (description "Resistor 10k")
      (fields
        (field (name "MANUFACTURER_PART_NUMBER") "AC05000004707JAC00")
        (field (name "MOUSER PART NUMBER") "594-AC05W0R470J")
      )
      (libsource (lib "GH_SchematicLib") (part "Resistor0805"))
    )
    (comp (ref "SW1")
      (value "430456043736")
      (footprint "GH_PcbLib:4304x60437x6")
      (description "430456043736 WS-TATV THT Washable Tact Switch 12x12mm, SPST-NO, 12VDC, 50mA, 360g")
      (fields (field (name "MANUFACTURER") "Wurth Elektronik"))
      (libsource (lib "GH_SchematicLib") (part "430456043736"))
    )
    (comp (ref "SW2")
      (value "430456043736")
      (footprint "GH_PcbLib:4304x60437x6")
      (description "430456043736 WS-TATV THT Washable Tact Switch 12x12mm, SPST-NO, 12VDC, 50mA, 360g")
      (fields (field (name "MANUFACTURER") "Wurth Elektronik"))
      (libsource (lib "GH_SchematicLib") (part "430456043736"))
    )
    (comp (ref "U4")
      (value "SN74AHC1G09DBVR")
      (footprint "GH_PcbLib:SOT95P280X145-5N")
      (description "Logic Gate Sgl 2Inp Pos-AND Gate")
      (fields (field (name "MOUSER PART NUMBER") "595-SN74AHC1G09DBVR"))
      (libsource (lib "GH_SchematicLib") (part "SN74AHC1G09DBVR"))
    )
    (comp (ref "U5")
      (value "SN74AHC1G09DBVR")
      (footprint "GH_PcbLib:SOT95P280X145-5N")
      (description "Logic Gate Sgl 2Inp Pos-AND Gate")
      (fields (field (name "MOUSER PART NUMBER") "595-SN74AHC1G09DBVR"))
      (libsource (lib "GH_SchematicLib") (part "SN74AHC1G09DBVR"))
    )
    (comp (ref "U6")
      (value "SN74AHC1G09DBVR")
      (footprint "GH_PcbLib:SOT95P280X145-5N")
      (description "Logic Gate Sgl 2Inp Pos-AND Gate")
      (fields (field (name "MOUSER PART NUMBER") "595-SN74AHC1G09DBVR"))
      (libsource (lib "GH_SchematicLib") (part "SN74AHC1G09DBVR"))
    )
    (comp (ref "U7")
      (value "SN74AHC1G09DBVR")
      (footprint "GH_PcbLib:SOT95P280X145-5N")
      (description "Logic Gate Sgl 2Inp Pos-AND Gate")
      (fields (field (name "MOUSER PART NUMBER") "595-SN74AHC1G09DBVR"))
      (libsource (lib "GH_SchematicLib") (part "SN74AHC1G09DBVR"))
    )
    (comp (ref "VR1")
      (value "CG0603MLC-05E")
      (footprint "GH_PcbLib:VARC1608X55N")
      (description "Varistor CG0603MLC-05E")
      (fields (field (name "MOUSER PART NUMBER") "652-CG0603MLC-05E"))
      (libsource (lib "GH_SchematicLib") (part "CG0603MLC-05E"))
    )
    (comp (ref "VR2")
      (value "CG0603MLC-05E")
      (footprint "GH_PcbLib:VARC1608X55N")
      (description "Varistor CG0603MLC-05E")
      (fields (field (name "MOUSER PART NUMBER") "652-CG0603MLC-05E"))
      (libsource (lib "GH_SchematicLib") (part "CG0603MLC-05E"))
    )
    (comp (ref "Y1")
      (value "16MHZ")
      (footprint "GH_PcbLib:ABM7")
      (description "Crystal or Oscillator")
      (fields
        (field (name "MANUFACTURER_PART_NUMBER") "ABM7-16.000MHZ-D2Y-T")
        (field (name "MOUSER PART NUMBER") "815-ABM7-16-D2Y-T")
      )
      (libsource (lib "GH_SchematicLib") (part "ABM7-16.000MHZ-D2Y-T"))
    )
    (comp (ref "Y2")
      (value "16MHZ")
      (footprint "GH_PcbLib:ABM7")
      (description "Crystal or Oscillator")
      (fields
        (field (name "MANUFACTURER_PART_NUMBER") "ABM7-16.000MHZ-D2Y-T")
        (field (name "MOUSER PART NUMBER") "815-ABM7-16-D2Y-T")
      )
      (libsource (lib "GH_SchematicLib") (part "ABM7-16.000MHZ-D2Y-T"))
    )
  )
  (nets
    (net (code "1") (name "+3V3") (class "Default")
      (node (ref "C13") (pin "2") (pinfunction "2_2") (pintype "passive"))
      (node (ref "C16") (pin "2") (pinfunction "2_2") (pintype "passive"))
      (node (ref "IC5") (pin "4") (pinfunction "OUT_4") (pintype "power_in"))
      (node (ref "IC5") (pin "5") (pinfunction "ADJ_5") (pintype "input"))
      (node (ref "J1") (pin "4") (pinfunction "4_4") (pintype "passive"))
      (node (ref "P4") (pin "3") (pinfunction "3_3") (pintype "passive"))
      (node (ref "R28") (pin "1") (pinfunction "1_1") (pintype "passive"))
    )
    (net (code "2") (name "+5") (class "Default")
      (node (ref "C12") (pin "2") (pinfunction "2_2") (pintype "passive"))
      (node (ref "C14") (pin "2") (pinfunction "2_2") (pintype "passive"))
      (node (ref "C2") (pin "1") (pinfunction "P_1") (pintype "passive"))
      (node (ref "C6") (pin "2") (pinfunction "2_2") (pintype "passive"))
      (node (ref "IC2") (pin "31") (pinfunction "UVCC_31") (pintype "passive"))
      (node (ref "IC5") (pin "1") (pinfunction "SHDN_N_1") (pintype "input"))
      (node (ref "IC5") (pin "2") (pinfunction "IN_2") (pintype "power_in"))
      (node (ref "J1") (pin "5") (pinfunction "5_5") (pintype "passive"))
      (node (ref "L1") (pin "2") (pinfunction "2_2") (pintype "passive"))
      (node (ref "P4") (pin "1") (pinfunction "1_1") (pintype "passive"))
      (node (ref "R27") (pin "2") (pinfunction "2_2") (pintype "passive"))
    )
    (net (code "3") (name "+5V{slash}3V3") (class "Default")
      (node (ref "C15") (pin "2") (pinfunction "2_2") (pintype "passive"))
      (node (ref "C17") (pin "1") (pinfunction "1_1") (pintype "passive"))
      (node (ref "C26") (pin "2") (pinfunction "2_2") (pintype "passive"))
      (node (ref "C28") (pin "2") (pinfunction "2_2") (pintype "passive"))
      (node (ref "C29") (pin "2") (pinfunction "2_2") (pintype "passive"))
      (node (ref "C30") (pin "2") (pinfunction "2_2") (pintype "passive"))
      (node (ref "C34") (pin "2") (pinfunction "2_2") (pintype "passive"))
      (node (ref "C35") (pin "2") (pinfunction "2_2") (pintype "passive"))
      (node (ref "C37") (pin "2") (pinfunction "2_2") (pintype "passive"))
      (node (ref "C38") (pin "2") (pinfunction "2_2") (pintype "passive"))
      (node (ref "C39") (pin "2") (pinfunction "2_2") (pintype "passive"))
      (node (ref "C40") (pin "2") (pinfunction "2_2") (pintype "passive"))
      (node (ref "C41") (pin "2") (pinfunction "2_2") (pintype "passive"))
      (node (ref "C8") (pin "2") (pinfunction "2_2") (pintype "passive"))
      (node (ref "D5") (pin "1") (pinfunction "K_1") (pintype "passive"))
      (node (ref "D6") (pin "1") (pinfunction "K_1") (pintype "passive"))
      (node (ref "FB1") (pin "1") (pinfunction "1_1") (pintype "passive"))
      (node (ref "FB2") (pin "1") (pinfunction "1_1") (pintype "passive"))
      (node (ref "FB3") (pin "1") (pinfunction "1_1") (pintype "passive"))
      (node (ref "IC4") (pin "14") (pinfunction "VCCB_14") (pintype "passive"))
      (node (ref "J1") (pin "2") (pinfunction "2_2") (pintype "passive"))
      (node (ref "J5") (pin "02") (pinfunction "02_02") (pintype "passive"))
      (node (ref "J6") (pin "02") (pinfunction "02_02") (pintype "passive"))
      (node (ref "P10") (pin "1") (pinfunction "1_1") (pintype "passive"))
      (node (ref "P11") (pin "1") (pinfunction "1_1") (pintype "passive"))
      (node (ref "P4") (pin "2") (pinfunction "2_2") (pintype "passive"))
      (node (ref "P6") (pin "1") (pinfunction "1_1") (pintype "passive"))
      (node (ref "P7") (pin "1") (pinfunction "1_1") (pintype "passive"))
      (node (ref "P8") (pin "1") (pinfunction "1_1") (pintype "passive"))
      (node (ref "P9") (pin "1") (pinfunction "1_1") (pintype "passive"))
      (node (ref "R1") (pin "1") (pinfunction "1_1") (pintype "passive"))
      (node (ref "R14") (pin "2") (pinfunction "2_2") (pintype "passive"))
      (node (ref "R15") (pin "1") (pinfunction "1_1") (pintype "passive"))
      (node (ref "R17") (pin "1") (pinfunction "1_1") (pintype "passive"))
      (node (ref "R18") (pin "2") (pinfunction "2_2") (pintype "passive"))
      (node (ref "R19") (pin "2") (pinfunction "2_2") (pintype "passive"))
      (node (ref "R2") (pin "1") (pinfunction "1_1") (pintype "passive"))
      (node (ref "R20") (pin "2") (pinfunction "2_2") (pintype "passive"))
      (node (ref "R21") (pin "2") (pinfunction "2_2") (pintype "passive"))
      (node (ref "R27") (pin "1") (pinfunction "1_1") (pintype "passive"))
      (node (ref "R28") (pin "2") (pinfunction "2_2") (pintype "passive"))
      (node (ref "R3") (pin "1") (pinfunction "1_1") (pintype "passive"))
      (node (ref "R4") (pin "1") (pinfunction "1_1") (pintype "passive"))
      (node (ref "U4") (pin "5") (pinfunction "VCC_5") (pintype "passive"))
      (node (ref "U5") (pin "5") (pinfunction "VCC_5") (pintype "passive"))
      (node (ref "U6") (pin "5") (pinfunction "VCC_5") (pintype "passive"))
      (node (ref "U7") (pin "5") (pinfunction "VCC_5") (pintype "passive"))
    )
    (net (code "4") (name "+AREF") (class "Default")
      (node (ref "C21") (pin "2") (pinfunction "2_2") (pintype "passive"))
      (node (ref "C24") (pin "1") (pinfunction "1_1") (pintype "passive"))
      (node (ref "IC1") (pin "21") (pinfunction "AREF_21") (pintype "passive"))
      (node (ref "J4") (pin "8") (pinfunction "8_8") (pintype "passive"))
    )
    (net (code "5") (name "/+3V3_16U2_UCAP") (class "Default")
      (node (ref "C7") (pin "2") (pinfunction "2_2") (pintype "passive"))
      (node (ref "IC2") (pin "27") (pinfunction "UCAP_27") (pintype "passive"))
      (node (ref "R26") (pin "1") (pinfunction "1_1") (pintype "passive"))
    )
    (net (code "6") (name "/+5V_USB") (class "Default")
      (node (ref "C1") (pin "1") (pinfunction "P_1") (pintype "passive"))
      (node (ref "J7") (pin "1") (pinfunction "VBUS_1") (pintype "passive"))
      (node (ref "L1") (pin "1") (pinfunction "1_1") (pintype "passive"))
    )
    (net (code "7") (name "/+5V{slash}3V3_16U2") (class "Default")
      (node (ref "C3") (pin "2") (pinfunction "2_2") (pintype "passive"))
      (node (ref "C4") (pin "2") (pinfunction "2_2") (pintype "passive"))
      (node (ref "C5") (pin "2") (pinfunction "2_2") (pintype "passive"))
      (node (ref "FB1") (pin "2") (pinfunction "2_2") (pintype "passive"))
      (node (ref "IC2") (pin "32") (pinfunction "AVCC_32") (pintype "passive"))
      (node (ref "IC2") (pin "4") (pinfunction "VCC_4") (pintype "passive"))
      (node (ref "R26") (pin "2") (pinfunction "2_2") (pintype "passive"))
    )
    (net (code "8") (name "/+5V{slash}3V3_328P_AVCC") (class "Default")
      (node (ref "C22") (pin "2") (pinfunction "2_2") (pintype "passive"))
      (node (ref "C23") (pin "2") (pinfunction "2_2") (pintype "passive"))
      (node (ref "FB3") (pin "2") (pinfunction "2_2") (pintype "passive"))
      (node (ref "IC1") (pin "20") (pinfunction "AVCC_20") (pintype "passive"))
    )
    (net (code "9") (name "/+5V{slash}3V3_328P_VCC") (class "Default")
      (node (ref "C19") (pin "2") (pinfunction "2_2") (pintype "passive"))
      (node (ref "C20") (pin "2") (pinfunction "2_2") (pintype "passive"))
      (node (ref "FB2") (pin "2") (pinfunction "2_2") (pintype "passive"))
      (node (ref "IC1") (pin "7") (pinfunction "VCC_7") (pintype "passive"))
    )
    (net (code "10") (name "/16U2PROG_328P_RESETn") (class "Default")
      (node (ref "IC2") (pin "13") (pinfunction "/_~{HWB_}/_AIN6_/_T0_/_INT7)_PD7_13") (pintype "passive"))
      (node (ref "P1") (pin "2") (pinfunction "2_2") (pintype "passive"))
      (node (ref "R1") (pin "2") (pinfunction "2_2") (pintype "passive"))
    )
    (net (code "11") (name "/16U2_16MHZ_XTAL1") (class "Default")
      (node (ref "C10") (pin "2") (pinfunction "2_2") (pintype "passive"))
      (node (ref "IC2") (pin "1") (pinfunction "XTAL1_1") (pintype "passive"))
      (node (ref "R9") (pin "1") (pinfunction "1_1") (pintype "passive"))
      (node (ref "Y2") (pin "1") (pinfunction "X1_1") (pintype "passive"))
    )
    (net (code "12") (name "/16U2_16MHZ_XTAL2") (class "Default")
      (node (ref "C9") (pin "2") (pinfunction "2_2") (pintype "passive"))
      (node (ref "IC2") (pin "2") (pinfunction "(PC0)_XTAL2_2") (pintype "passive"))
      (node (ref "R9") (pin "2") (pinfunction "2_2") (pintype "passive"))
      (node (ref "Y2") (pin "2") (pinfunction "X2_2") (pintype "passive"))
    )
    (net (code "13") (name "/16U2_BUF_RESETn") (class "Default")
      (node (ref "C31") (pin "2") (pinfunction "2_2") (pintype "passive"))
      (node (ref "R23") (pin "2") (pinfunction "2_2") (pintype "passive"))
      (node (ref "U5") (pin "1") (pinfunction "A_1") (pintype "passive"))
      (node (ref "U5") (pin "2") (pinfunction "B_2") (pintype "passive"))
    )
    (net (code "14") (name "/16U2_HDR_RESETn") (class "Default")
      (node (ref "J6") (pin "05") (pinfunction "05_05") (pintype "passive"))
      (node (ref "P3") (pin "3") (pinfunction "3_3") (pintype "passive"))
    )
    (net (code "15") (name "/16U2_PB4") (class "Default")
      (node (ref "IC2") (pin "18") (pinfunction "PB4_(T1_/_PCINT4)_18") (pintype "passive"))
      (node (ref "P2") (pin "1") (pinfunction "1_1") (pintype "passive"))
      (node (ref "P3") (pin "2") (pinfunction "2_2") (pintype "passive"))
    )
    (net (code "16") (name "/16U2_PB5") (class "Default")
      (node (ref "IC2") (pin "19") (pinfunction "PB5_(PCINT5)_19") (pintype "passive"))
      (node (ref "P2") (pin "3") (pinfunction "3_3") (pintype "passive"))
    )
    (net (code "17") (name "/16U2_PB6") (class "Default")
      (node (ref "IC2") (pin "20") (pinfunction "PB6_(PCINT6)_20") (pintype "passive"))
      (node (ref "P2") (pin "2") (pinfunction "2_2") (pintype "passive"))
    )
    (net (code "18") (name "/16U2_PB7") (class "Default")
      (node (ref "IC2") (pin "21") (pinfunction "PB7_(PCINT7_/_OC.0A_/_OC.1C)_21") (pintype "passive"))
      (node (ref "P2") (pin "4") (pinfunction "4_4") (pintype "passive"))
    )
    (net (code "19") (name "/16U2_RESETn") (class "Default")
      (node (ref "IC2") (pin "24") (pinfunction "~{RESET_(PC1_}/_DW)_24") (pintype "passive"))
      (node (ref "P3") (pin "4") (pinfunction "4_4") (pintype "passive"))
      (node (ref "R4") (pin "2") (pinfunction "2_2") (pintype "passive"))
      (node (ref "U5") (pin "4") (pinfunction "Y_4") (pintype "passive"))
    )
    (net (code "20") (name "/16U2_SCLK") (class "Default")
      (node (ref "J6") (pin "03") (pinfunction "03_03") (pintype "passive"))
      (node (ref "R5") (pin "1") (pinfunction "1_1") (pintype "passive"))
    )
    (net (code "21") (name "/328P_16MHZ_XTAL1") (class "Default")
      (node (ref "C27") (pin "2") (pinfunction "2_2") (pintype "passive"))
      (node (ref "IC1") (pin "9") (pinfunction "PB6_(PCINT6/XTAL1/TOSC1)_9") (pintype "passive"))
      (node (ref "R16") (pin "2") (pinfunction "2_2") (pintype "passive"))
      (node (ref "Y1") (pin "1") (pinfunction "X1_1") (pintype "passive"))
    )
    (net (code "22") (name "/328P_16MHZ_XTAL2") (class "Default")
      (node (ref "C25") (pin "2") (pinfunction "2_2") (pintype "passive"))
      (node (ref "IC1") (pin "10") (pinfunction "PB7_(PCINT7/XTAL2/TOSC2)_10") (pintype "passive"))
      (node (ref "R16") (pin "1") (pinfunction "1_1") (pintype "passive"))
      (node (ref "Y1") (pin "2") (pinfunction "X2_2") (pintype "passive"))
    )
    (net (code "23") (name "/328P_AUTORESETn") (class "Default")
      (node (ref "C11") (pin "2") (pinfunction "2_2") (pintype "passive"))
      (node (ref "R18") (pin "1") (pinfunction "1_1") (pintype "passive"))
      (node (ref "U6") (pin "1") (pinfunction "A_1") (pintype "passive"))
    )
    (net (code "24") (name "/328P_BUF_RESETn") (class "Default")
      (node (ref "C32") (pin "2") (pinfunction "2_2") (pintype "passive"))
      (node (ref "R24") (pin "2") (pinfunction "2_2") (pintype "passive"))
      (node (ref "U6") (pin "2") (pinfunction "B_2") (pintype "passive"))
    )
    (net (code "25") (name "/328P_RESETn") (class "Default")
      (node (ref "IC1") (pin "1") (pinfunction "PC6_(PCINT14/~{RESET)}_1") (pintype "passive"))
      (node (ref "J1") (pin "3") (pinfunction "3_3") (pintype "passive"))
      (node (ref "J5") (pin "05") (pinfunction "05_05") (pintype "passive"))
      (node (ref "P3") (pin "1") (pinfunction "1_1") (pintype "passive"))
      (node (ref "R14") (pin "1") (pinfunction "1_1") (pintype "passive"))
      (node (ref "U6") (pin "4") (pinfunction "Y_4") (pintype "passive"))
    )
    (net (code "26") (name "/AD0") (class "Default")
      (node (ref "IC1") (pin "23") (pinfunction "PC0_(ADC0/PCINT8)_23") (pintype "passive"))
      (node (ref "J2") (pin "1") (pinfunction "1_1") (pintype "passive"))
    )
    (net (code "27") (name "/AD1") (class "Default")
      (node (ref "IC1") (pin "24") (pinfunction "PC1_(ADC1/PCINT9)_24") (pintype "passive"))
      (node (ref "J2") (pin "2") (pinfunction "2_2") (pintype "passive"))
    )
    (net (code "28") (name "/AD2") (class "Default")
      (node (ref "IC1") (pin "25") (pinfunction "PC2_(ADC2/PCINT10)_25") (pintype "passive"))
      (node (ref "J2") (pin "3") (pinfunction "3_3") (pintype "passive"))
    )
    (net (code "29") (name "/AD3") (class "Default")
      (node (ref "IC1") (pin "26") (pinfunction "PC3_(ADC3/PCINT11)_26") (pintype "passive"))
      (node (ref "J2") (pin "4") (pinfunction "4_4") (pintype "passive"))
    )
    (net (code "30") (name "/AD4{slash}SDA") (class "Default")
      (node (ref "IC1") (pin "27") (pinfunction "PC4_(ADC4/SDA/PCINT12)_27") (pintype "passive"))
      (node (ref "J2") (pin "5") (pinfunction "5_5") (pintype "passive"))
      (node (ref "J4") (pin "9") (pinfunction "9_9") (pintype "passive"))
      (node (ref "P6") (pin "4") (pinfunction "4_4") (pintype "passive"))
    )
    (net (code "31") (name "/AD5{slash}SCL") (class "Default")
      (node (ref "IC1") (pin "28") (pinfunction "PC5_(ADC5/SCL/PCINT13)_28") (pintype "passive"))
      (node (ref "J2") (pin "6") (pinfunction "6_6") (pintype "passive"))
      (node (ref "J4") (pin "10") (pinfunction "10_10") (pintype "passive"))
      (node (ref "P6") (pin "3") (pinfunction "3_3") (pintype "passive"))
    )
    (net (code "32") (name "/BUTTON_RESETn") (class "Default")
      (node (ref "D6") (pin "2") (pinfunction "A_2") (pintype "passive"))
      (node (ref "R20") (pin "1") (pinfunction "1_1") (pintype "passive"))
      (node (ref "R24") (pin "1") (pinfunction "1_1") (pintype "passive"))
      (node (ref "SW1") (pin "B1") (pinfunction "B1_B1") (pintype "passive"))
      (node (ref "SW1") (pin "B2") (pinfunction "B2_B2") (pintype "passive"))
    )
    (net (code "33") (name "/CON_USB_N") (class "Default")
      (node (ref "J7") (pin "2") (pinfunction "D-_2") (pintype "passive"))
      (node (ref "R6") (pin "1") (pinfunction "1_1") (pintype "passive"))
      (node (ref "VR1") (pin "2") (pinfunction "2_2") (pintype "passive"))
    )
    (net (code "34") (name "/CON_USB_P") (class "Default")
      (node (ref "J7") (pin "3") (pinfunction "D+_3") (pintype "passive"))
      (node (ref "R7") (pin "1") (pinfunction "1_1") (pintype "passive"))
      (node (ref "VR2") (pin "2") (pinfunction "2_2") (pintype "passive"))
    )
    (net (code "35") (name "/IO0") (class "Default")
      (node (ref "IC1") (pin "2") (pinfunction "PD0_(PCINT16/RXD)_2") (pintype "passive"))
      (node (ref "IC4") (pin "13") (pinfunction "B1_13") (pintype "passive"))
      (node (ref "J3") (pin "1") (pinfunction "1_1") (pintype "passive"))
      (node (ref "R10") (pin "2") (pinfunction "2_2") (pintype "passive"))
    )
    (net (code "36") (name "/IO1") (class "Default")
      (node (ref "IC1") (pin "3") (pinfunction "PD1_(PCINT17/TXD)_3") (pintype "passive"))
      (node (ref "IC4") (pin "12") (pinfunction "B2_12") (pintype "passive"))
      (node (ref "J3") (pin "2") (pinfunction "2_2") (pintype "passive"))
      (node (ref "R11") (pin "2") (pinfunction "2_2") (pintype "passive"))
    )
    (net (code "37") (name "/IO2") (class "Default")
      (node (ref "IC1") (pin "4") (pinfunction "PD2_(PCINT18/INT0)_4") (pintype "passive"))
      (node (ref "J3") (pin "3") (pinfunction "3_3") (pintype "passive"))
      (node (ref "P7") (pin "2") (pinfunction "2_2") (pintype "passive"))
    )
    (net (code "38") (name "/IO3") (class "Default")
      (node (ref "IC1") (pin "5") (pinfunction "PD3_(PCINT19/OC2B/INT1)_5") (pintype "passive"))
      (node (ref "J3") (pin "4") (pinfunction "4_4") (pintype "passive"))
      (node (ref "P8") (pin "2") (pinfunction "2_2") (pintype "passive"))
    )
    (net (code "39") (name "/IO4") (class "Default")
      (node (ref "IC1") (pin "6") (pinfunction "PD4_(PCINT20/XCK/T0)_6") (pintype "passive"))
      (node (ref "J3") (pin "5") (pinfunction "5_5") (pintype "passive"))
      (node (ref "P9") (pin "2") (pinfunction "2_2") (pintype "passive"))
    )
    (net (code "40") (name "/IO5") (class "Default")
      (node (ref "IC1") (pin "11") (pinfunction "PD5_(PCINT21/OC0B/T1)_11") (pintype "passive"))
      (node (ref "J3") (pin "6") (pinfunction "6_6") (pintype "passive"))
      (node (ref "P10") (pin "2") (pinfunction "2_2") (pintype "passive"))
    )
    (net (code "41") (name "/IO6") (class "Default")
      (node (ref "IC1") (pin "12") (pinfunction "PD6_(PCINT22/OC0A/AIN0)_12") (pintype "passive"))
      (node (ref "J3") (pin "7") (pinfunction "7_7") (pintype "passive"))
      (node (ref "P11") (pin "2") (pinfunction "2_2") (pintype "passive"))
    )
    (net (code "42") (name "/IO7") (class "Default")
      (node (ref "IC1") (pin "13") (pinfunction "PD7_(PCINT23/AIN1)_13") (pintype "passive"))
      (node (ref "J3") (pin "8") (pinfunction "8_8") (pintype "passive"))
    )
    (net (code "43") (name "/IO8") (class "Default")
      (node (ref "IC1") (pin "14") (pinfunction "PB0_(PCINT0/CLKO/ICP1)_14") (pintype "passive"))
      (node (ref "IC4") (pin "11") (pinfunction "B3_11") (pintype "passive"))
      (node (ref "J4") (pin "1") (pinfunction "1_1") (pintype "passive"))
      (node (ref "R22") (pin "2") (pinfunction "2_2") (pintype "passive"))
    )
    (net (code "44") (name "/IO9") (class "Default")
      (node (ref "IC1") (pin "15") (pinfunction "PB1_(OC1A/PCINT1)_15") (pintype "passive"))
      (node (ref "IC4") (pin "10") (pinfunction "B4_10") (pintype "passive"))
      (node (ref "J4") (pin "2") (pinfunction "2_2") (pintype "passive"))
    )
    (net (code "45") (name "/LVL_A1") (class "Default")
      (node (ref "IC4") (pin "2") (pinfunction "A1_2") (pintype "passive"))
      (node (ref "J8") (pin "2") (pinfunction "2_2") (pintype "passive"))
    )
    (net (code "46") (name "/LVL_A2") (class "Default")
      (node (ref "IC4") (pin "3") (pinfunction "A2_3") (pintype "passive"))
      (node (ref "J8") (pin "3") (pinfunction "3_3") (pintype "passive"))
    )
    (net (code "47") (name "/LVL_A3") (class "Default")
      (node (ref "IC4") (pin "4") (pinfunction "A3_4") (pintype "passive"))
      (node (ref "J8") (pin "4") (pinfunction "4_4") (pintype "passive"))
    )
    (net (code "48") (name "/LVL_A4") (class "Default")
      (node (ref "IC4") (pin "5") (pinfunction "A4_5") (pintype "passive"))
      (node (ref "J8") (pin "5") (pinfunction "5_5") (pintype "passive"))
    )
    (net (code "49") (name "/LVL_VCCA") (class "Default")
      (node (ref "C36") (pin "1") (pinfunction "1_1") (pintype "passive"))
      (node (ref "IC4") (pin "1") (pinfunction "VCCA_1") (pintype "passive"))
      (node (ref "J8") (pin "1") (pinfunction "1_1") (pintype "passive"))
    )
    (net (code "50") (name "/MISO") (class "Default")
      (node (ref "IC1") (pin "18") (pinfunction "PB4_(MISO/PCINT4)_18") (pintype "passive"))
      (node (ref "J4") (pin "5") (pinfunction "5_5") (pintype "passive"))
      (node (ref "J5") (pin "01") (pinfunction "01_01") (pintype "passive"))
    )
    (net (code "51") (name "/MOSI") (class "Default")
      (node (ref "IC1") (pin "17") (pinfunction "PB3_(MOSI/OC2A/PCINT3)_17") (pintype "passive"))
      (node (ref "J4") (pin "4") (pinfunction "4_4") (pintype "passive"))
      (node (ref "J5") (pin "04") (pinfunction "04_04") (pintype "passive"))
    )
    (net (code "52") (name "/SCK") (class "Default")
      (node (ref "J4") (pin "6") (pinfunction "6_6") (pintype "passive"))
      (node (ref "J5") (pin "03") (pinfunction "03_03") (pintype "passive"))
      (node (ref "R13") (pin "2") (pinfunction "2_2") (pintype "passive"))
      (node (ref "U4") (pin "1") (pinfunction "A_1") (pintype "passive"))
      (node (ref "U4") (pin "2") (pinfunction "B_2") (pintype "passive"))
    )
    (net (code "53") (name "/SCK_R") (class "Default")
      (node (ref "IC1") (pin "19") (pinfunction "PB5_(SCK/PCINT5)_19") (pintype "passive"))
      (node (ref "R13") (pin "1") (pinfunction "1_1") (pintype "passive"))
    )
    (net (code "54") (name "/SS") (class "Default")
      (node (ref "IC1") (pin "16") (pinfunction "PB2_(~{SS}/OC1B/PCINT2)_16") (pintype "passive"))
      (node (ref "J4") (pin "3") (pinfunction "3_3") (pintype "passive"))
    )
    (net (code "55") (name "/USB_N") (class "Default")
      (node (ref "IC2") (pin "30") (pinfunction "D-_30") (pintype "passive"))
      (node (ref "R6") (pin "2") (pinfunction "2_2") (pintype "passive"))
    )
    (net (code "56") (name "/USB_P") (class "Default")
      (node (ref "IC2") (pin "29") (pinfunction "D+_29") (pintype "passive"))
      (node (ref "R7") (pin "2") (pinfunction "2_2") (pintype "passive"))
    )
    (net (code "57") (name "/USER_BUTTON") (class "Default")
      (node (ref "R21") (pin "1") (pinfunction "1_1") (pintype "passive"))
      (node (ref "R25") (pin "1") (pinfunction "1_1") (pintype "passive"))
      (node (ref "SW2") (pin "B1") (pinfunction "B1_B1") (pintype "passive"))
      (node (ref "SW2") (pin "B2") (pinfunction "B2_B2") (pintype "passive"))
    )
    (net (code "58") (name "/USER_BUTTON_BUF") (class "Default")
      (node (ref "C33") (pin "2") (pinfunction "2_2") (pintype "passive"))
      (node (ref "R25") (pin "2") (pinfunction "2_2") (pintype "passive"))
      (node (ref "U7") (pin "1") (pinfunction "A_1") (pintype "passive"))
      (node (ref "U7") (pin "2") (pinfunction "B_2") (pintype "passive"))
    )
    (net (code "59") (name "GND") (class "Default")
      (node (ref "C1") (pin "2") (pinfunction "N_2") (pintype "passive"))
      (node (ref "C10") (pin "1") (pinfunction "1_1") (pintype "passive"))
      (node (ref "C12") (pin "1") (pinfunction "1_1") (pintype "passive"))
      (node (ref "C13") (pin "1") (pinfunction "1_1") (pintype "passive"))
      (node (ref "C14") (pin "1") (pinfunction "1_1") (pintype "passive"))
      (node (ref "C15") (pin "1") (pinfunction "1_1") (pintype "passive"))
      (node (ref "C16") (pin "1") (pinfunction "1_1") (pintype "passive"))
      (node (ref "C17") (pin "2") (pinfunction "2_2") (pintype "passive"))
      (node (ref "C19") (pin "1") (pinfunction "1_1") (pintype "passive"))
      (node (ref "C2") (pin "2") (pinfunction "N_2") (pintype "passive"))
      (node (ref "C20") (pin "1") (pinfunction "1_1") (pintype "passive"))
      (node (ref "C21") (pin "1") (pinfunction "1_1") (pintype "passive"))
      (node (ref "C22") (pin "1") (pinfunction "1_1") (pintype "passive"))
      (node (ref "C23") (pin "1") (pinfunction "1_1") (pintype "passive"))
      (node (ref "C24") (pin "2") (pinfunction "2_2") (pintype "passive"))
      (node (ref "C25") (pin "1") (pinfunction "1_1") (pintype "passive"))
      (node (ref "C26") (pin "1") (pinfunction "1_1") (pintype "passive"))
      (node (ref "C27") (pin "1") (pinfunction "1_1") (pintype "passive"))
      (node (ref "C28") (pin "1") (pinfunction "1_1") (pintype "passive"))
      (node (ref "C29") (pin "1") (pinfunction "1_1") (pintype "passive"))
      (node (ref "C3") (pin "1") (pinfunction "1_1") (pintype "passive"))
      (node (ref "C30") (pin "1") (pinfunction "1_1") (pintype "passive"))
      (node (ref "C31") (pin "1") (pinfunction "1_1") (pintype "passive"))
      (node (ref "C32") (pin "1") (pinfunction "1_1") (pintype "passive"))
      (node (ref "C33") (pin "1") (pinfunction "1_1") (pintype "passive"))
      (node (ref "C34") (pin "1") (pinfunction "1_1") (pintype "passive"))
      (node (ref "C35") (pin "1") (pinfunction "1_1") (pintype "passive"))
      (node (ref "C36") (pin "2") (pinfunction "2_2") (pintype "passive"))
      (node (ref "C37") (pin "1") (pinfunction "1_1") (pintype "passive"))
      (node (ref "C38") (pin "1") (pinfunction "1_1") (pintype "passive"))
      (node (ref "C39") (pin "1") (pinfunction "1_1") (pintype "passive"))
      (node (ref "C4") (pin "1") (pinfunction "1_1") (pintype "passive"))
      (node (ref "C40") (pin "1") (pinfunction "1_1") (pintype "passive"))
      (node (ref "C41") (pin "1") (pinfunction "1_1") (pintype "passive"))
      (node (ref "C5") (pin "1") (pinfunction "1_1") (pintype "passive"))
      (node (ref "C6") (pin "1") (pinfunction "1_1") (pintype "passive"))
      (node (ref "C7") (pin "1") (pinfunction "1_1") (pintype "passive"))
      (node (ref "C8") (pin "1") (pinfunction "1_1") (pintype "passive"))
      (node (ref "C9") (pin "1") (pinfunction "1_1") (pintype "passive"))
      (node (ref "D1") (pin "1") (pinfunction "K_1") (pintype "passive"))
      (node (ref "IC1") (pin "22") (pinfunction "GND_2_22") (pintype "passive"))
      (node (ref "IC1") (pin "8") (pinfunction "GND_1_8") (pintype "passive"))
      (node (ref "IC2") (pin "28") (pinfunction "UGND_28") (pintype "passive"))
      (node (ref "IC2") (pin "3") (pinfunction "GND_3") (pintype "passive"))
      (node (ref "IC4") (pin "7") (pinfunction "GND_7") (pintype "passive"))
      (node (ref "IC5") (pin "3") (pinfunction "GND_3") (pintype "power_in"))
      (node (ref "IC5") (pin "6") (pinfunction "PAD_6") (pintype "power_in"))
      (node (ref "J1") (pin "6") (pinfunction "6_6") (pintype "passive"))
      (node (ref "J1") (pin "7") (pinfunction "7_7") (pintype "passive"))
      (node (ref "J4") (pin "7") (pinfunction "7_7") (pintype "passive"))
      (node (ref "J5") (pin "06") (pinfunction "06_06") (pintype "passive"))
      (node (ref "J6") (pin "06") (pinfunction "06_06") (pintype "passive"))
      (node (ref "J7") (pin "5") (pinfunction "GND_5") (pintype "passive"))
      (node (ref "J7") (pin "Shell") (pinfunction "Shield_Shell") (pintype "passive"))
      (node (ref "J8") (pin "6") (pinfunction "6_6") (pintype "passive"))
      (node (ref "MH1") (pin "1") (pinfunction "1_1") (pintype "passive"))
      (node (ref "MH2") (pin "1") (pinfunction "1_1") (pintype "passive"))
      (node (ref "MH3") (pin "1") (pinfunction "1_1") (pintype "passive"))
      (node (ref "MH4") (pin "1") (pinfunction "1_1") (pintype "passive"))
      (node (ref "MS1") (pin "1") (pinfunction "1_1") (pintype "passive"))
      (node (ref "MS2") (pin "1") (pinfunction "1_1") (pintype "passive"))
      (node (ref "P10") (pin "3") (pinfunction "3_3") (pintype "passive"))
      (node (ref "P11") (pin "3") (pinfunction "3_3") (pintype "passive"))
      (node (ref "P6") (pin "2") (pinfunction "2_2") (pintype "passive"))
      (node (ref "P7") (pin "3") (pinfunction "3_3") (pintype "passive"))
      (node (ref "P8") (pin "3") (pinfunction "3_3") (pintype "passive"))
      (node (ref "P9") (pin "3") (pinfunction "3_3") (pintype "passive"))
      (node (ref "R12") (pin "1") (pinfunction "1_1") (pintype "passive"))
      (node (ref "R29") (pin "1") (pinfunction "1_1") (pintype "passive"))
      (node (ref "R8") (pin "1") (pinfunction "1_1") (pintype "passive"))
      (node (ref "SW1") (pin "A1") (pinfunction "A1_A1") (pintype "passive"))
      (node (ref "SW1") (pin "A2") (pinfunction "A2_A2") (pintype "passive"))
      (node (ref "SW2") (pin "A1") (pinfunction "A1_A1") (pintype "passive"))
      (node (ref "SW2") (pin "A2") (pinfunction "A2_A2") (pintype "passive"))
      (node (ref "U4") (pin "3") (pinfunction "GND_3") (pintype "passive"))
      (node (ref "U5") (pin "3") (pinfunction "GND_3") (pintype "passive"))
      (node (ref "U6") (pin "3") (pinfunction "GND_3") (pintype "passive"))
      (node (ref "U7") (pin "3") (pinfunction "GND_3") (pintype "passive"))
      (node (ref "VR1") (pin "1") (pinfunction "1_1") (pintype "passive"))
      (node (ref "VR2") (pin "1") (pinfunction "1_1") (pintype "passive"))
    )
    (net (code "60") (name "Net-(C11-Pad1)") (class "Default")
      (node (ref "C11") (pin "1") (pinfunction "1_1") (pintype "passive"))
      (node (ref "P1") (pin "1") (pinfunction "1_1") (pintype "passive"))
    )
    (net (code "61") (name "Net-(D1-A)") (class "Default")
      (node (ref "D1") (pin "2") (pinfunction "A_2") (pintype "passive"))
      (node (ref "R17") (pin "2") (pinfunction "2_2") (pintype "passive"))
    )
    (net (code "62") (name "Net-(D2-A)") (class "Default")
      (node (ref "D2") (pin "2") (pinfunction "A_2") (pintype "passive"))
      (node (ref "R15") (pin "2") (pinfunction "2_2") (pintype "passive"))
    )
    (net (code "63") (name "Net-(D2-K)") (class "Default")
      (node (ref "D2") (pin "1") (pinfunction "K_1") (pintype "passive"))
      (node (ref "U4") (pin "4") (pinfunction "Y_4") (pintype "passive"))
    )
    (net (code "64") (name "Net-(D3-A)") (class "Default")
      (node (ref "D3") (pin "2") (pinfunction "A_2") (pintype "passive"))
      (node (ref "R2") (pin "2") (pinfunction "2_2") (pintype "passive"))
    )
    (net (code "65") (name "Net-(D3-K)") (class "Default")
      (node (ref "D3") (pin "1") (pinfunction "K_1") (pintype "passive"))
      (node (ref "IC2") (pin "11") (pinfunction "(XCK_AIN4_/_PCINT12)_PD5_11") (pintype "passive"))
    )
    (net (code "66") (name "Net-(D4-A)") (class "Default")
      (node (ref "D4") (pin "2") (pinfunction "A_2") (pintype "passive"))
      (node (ref "R3") (pin "2") (pinfunction "2_2") (pintype "passive"))
    )
    (net (code "67") (name "Net-(D4-K)") (class "Default")
      (node (ref "D4") (pin "1") (pinfunction "K_1") (pintype "passive"))
      (node (ref "IC2") (pin "10") (pinfunction "(INT5/_AIN3)_PD4_10") (pintype "passive"))
    )
    (net (code "68") (name "Net-(D5-A)") (class "Default")
      (node (ref "D5") (pin "2") (pinfunction "A_2") (pintype "passive"))
      (node (ref "R19") (pin "1") (pinfunction "1_1") (pintype "passive"))
      (node (ref "R23") (pin "1") (pinfunction "1_1") (pintype "passive"))
    )
    (net (code "69") (name "Net-(IC2-(PDI_{slash}_MOSI_{slash}_PCINT2)_PB2)") (class "Default")
      (node (ref "IC2") (pin "16") (pinfunction "(PDI_/_MOSI_/_PCINT2)_PB2_16") (pintype "passive"))
      (node (ref "J6") (pin "04") (pinfunction "04_04") (pintype "passive"))
    )
    (net (code "70") (name "Net-(IC2-(RXD1_{slash}_AIN1_{slash}_INT2)_PD2)") (class "Default")
      (node (ref "IC2") (pin "8") (pinfunction "(RXD1_/_AIN1_/_INT2)_PD2_8") (pintype "passive"))
      (node (ref "R11") (pin "1") (pinfunction "1_1") (pintype "passive"))
    )
    (net (code "71") (name "Net-(IC2-(SCLK_{slash}_PCINT1)_PB1)") (class "Default")
      (node (ref "IC2") (pin "15") (pinfunction "(SCLK_/_PCINT1)_PB1_15") (pintype "passive"))
      (node (ref "R5") (pin "2") (pinfunction "2_2") (pintype "passive"))
    )
    (net (code "72") (name "Net-(IC2-(TXD1_{slash}_INT3)_PD3)") (class "Default")
      (node (ref "IC2") (pin "9") (pinfunction "(TXD1_/_INT3)_PD3_9") (pintype "passive"))
      (node (ref "R10") (pin "1") (pinfunction "1_1") (pintype "passive"))
    )
    (net (code "73") (name "Net-(IC2-PB3_(PDO_{slash}_MISO_{slash}_PCINT3))") (class "Default")
      (node (ref "IC2") (pin "17") (pinfunction "PB3_(PDO_/_MISO_/_PCINT3)_17") (pintype "passive"))
      (node (ref "J6") (pin "01") (pinfunction "01_01") (pintype "passive"))
    )
    (net (code "74") (name "Net-(IC4-OE)") (class "Default")
      (node (ref "IC4") (pin "8") (pinfunction "OE_8") (pintype "passive"))
      (node (ref "P5") (pin "1") (pinfunction "1_1") (pintype "passive"))
    )
    (net (code "75") (name "Net-(J7-ID)") (class "Default")
      (node (ref "J7") (pin "4") (pinfunction "ID_4") (pintype "passive"))
      (node (ref "R8") (pin "2") (pinfunction "2_2") (pintype "passive"))
    )
    (net (code "76") (name "Net-(P1-Pad3)") (class "Default")
      (node (ref "P1") (pin "3") (pinfunction "3_3") (pintype "passive"))
      (node (ref "R12") (pin "2") (pinfunction "2_2") (pintype "passive"))
    )
    (net (code "77") (name "Net-(P5-Pad2)") (class "Default")
      (node (ref "P5") (pin "2") (pinfunction "2_2") (pintype "passive"))
      (node (ref "R29") (pin "2") (pinfunction "2_2") (pintype "passive"))
    )
    (net (code "78") (name "Net-(U7-Y)") (class "Default")
      (node (ref "R22") (pin "1") (pinfunction "1_1") (pintype "passive"))
      (node (ref "U7") (pin "4") (pinfunction "Y_4") (pintype "passive"))
    )
    (net (code "79") (name "unconnected-(IC2-(AIN0_{slash}_INT1)_PD1-Pad7)") (class "Default")
      (node (ref "IC2") (pin "7") (pinfunction "(AIN0_/_INT1)_PD1_7") (pintype "passive+no_connect"))
    )
    (net (code "80") (name "unconnected-(IC2-(OC.0B_{slash}_INT0)_PD0-Pad6)") (class "Default")
      (node (ref "IC2") (pin "6") (pinfunction "(OC.0B_/_INT0)_PD0_6") (pintype "passive+no_connect"))
    )
    (net (code "81") (name "unconnected-(IC2-(PCINT11_{slash}AIN2_)_PC2-Pad5)") (class "Default")
      (node (ref "IC2") (pin "5") (pinfunction "(PCINT11_/AIN2_)_PC2_5") (pintype "passive+no_connect"))
    )
    (net (code "82") (name "unconnected-(IC2-(~{RTS_}{slash}_AIN5_{slash}_INT6)_PD6-Pad12)") (class "Default")
      (node (ref "IC2") (pin "12") (pinfunction "(~{RTS_}/_AIN5_/_INT6)_PD6_12") (pintype "passive+no_connect"))
    )
    (net (code "83") (name "unconnected-(IC2-(~{SS_}{slash}_PCINT0)_PB0-Pad14)") (class "Default")
      (node (ref "IC2") (pin "14") (pinfunction "(~{SS_}/_PCINT0)_PB0_14") (pintype "passive+no_connect"))
    )
    (net (code "84") (name "unconnected-(IC2-PC4_(PCINT10)-Pad26)") (class "Default")
      (node (ref "IC2") (pin "26") (pinfunction "PC4_(PCINT10)_26") (pintype "passive+no_connect"))
    )
    (net (code "85") (name "unconnected-(IC2-PC5_(_PCINT9{slash}_OC.1B)-Pad25)") (class "Default")
      (node (ref "IC2") (pin "25") (pinfunction "PC5_(_PCINT9/_OC.1B)_25") (pintype "passive+no_connect"))
    )
    (net (code "86") (name "unconnected-(IC2-PC6_(OC.1A_{slash}_PCINT8)-Pad23)") (class "Default")
      (node (ref "IC2") (pin "23") (pinfunction "PC6_(OC.1A_/_PCINT8)_23") (pintype "passive+no_connect"))
    )
    (net (code "87") (name "unconnected-(IC2-PC7_(INT4_{slash}_ICP1_{slash}_CLKO)-Pad22)") (class "Default")
      (node (ref "IC2") (pin "22") (pinfunction "PC7_(INT4_/_ICP1_/_CLKO)_22") (pintype "passive+no_connect"))
    )
    (net (code "88") (name "unconnected-(IC4-NC_1-Pad6)") (class "Default")
      (node (ref "IC4") (pin "6") (pinfunction "NC_1_6") (pintype "passive+no_connect"))
    )
    (net (code "89") (name "unconnected-(IC4-NC_2-Pad9)") (class "Default")
      (node (ref "IC4") (pin "9") (pinfunction "NC_2_9") (pintype "passive+no_connect"))
    )
    (net (code "90") (name "unconnected-(J1-Pad1)") (class "Default")
      (node (ref "J1") (pin "1") (pinfunction "1_1") (pintype "passive+no_connect"))
    )
    (net (code "91") (name "unconnected-(J1-Pad8)") (class "Default")
      (node (ref "J1") (pin "8") (pinfunction "8_8") (pintype "passive+no_connect"))
    )
    (net (code "92") (name "unconnected-(P5-Pad3)") (class "Default")
      (node (ref "P5") (pin "3") (pinfunction "3_3") (pintype "passive+no_connect"))
    )
  )
)
